# Supply.net
KiCad netlist of a schematic drawn in Altium Designer
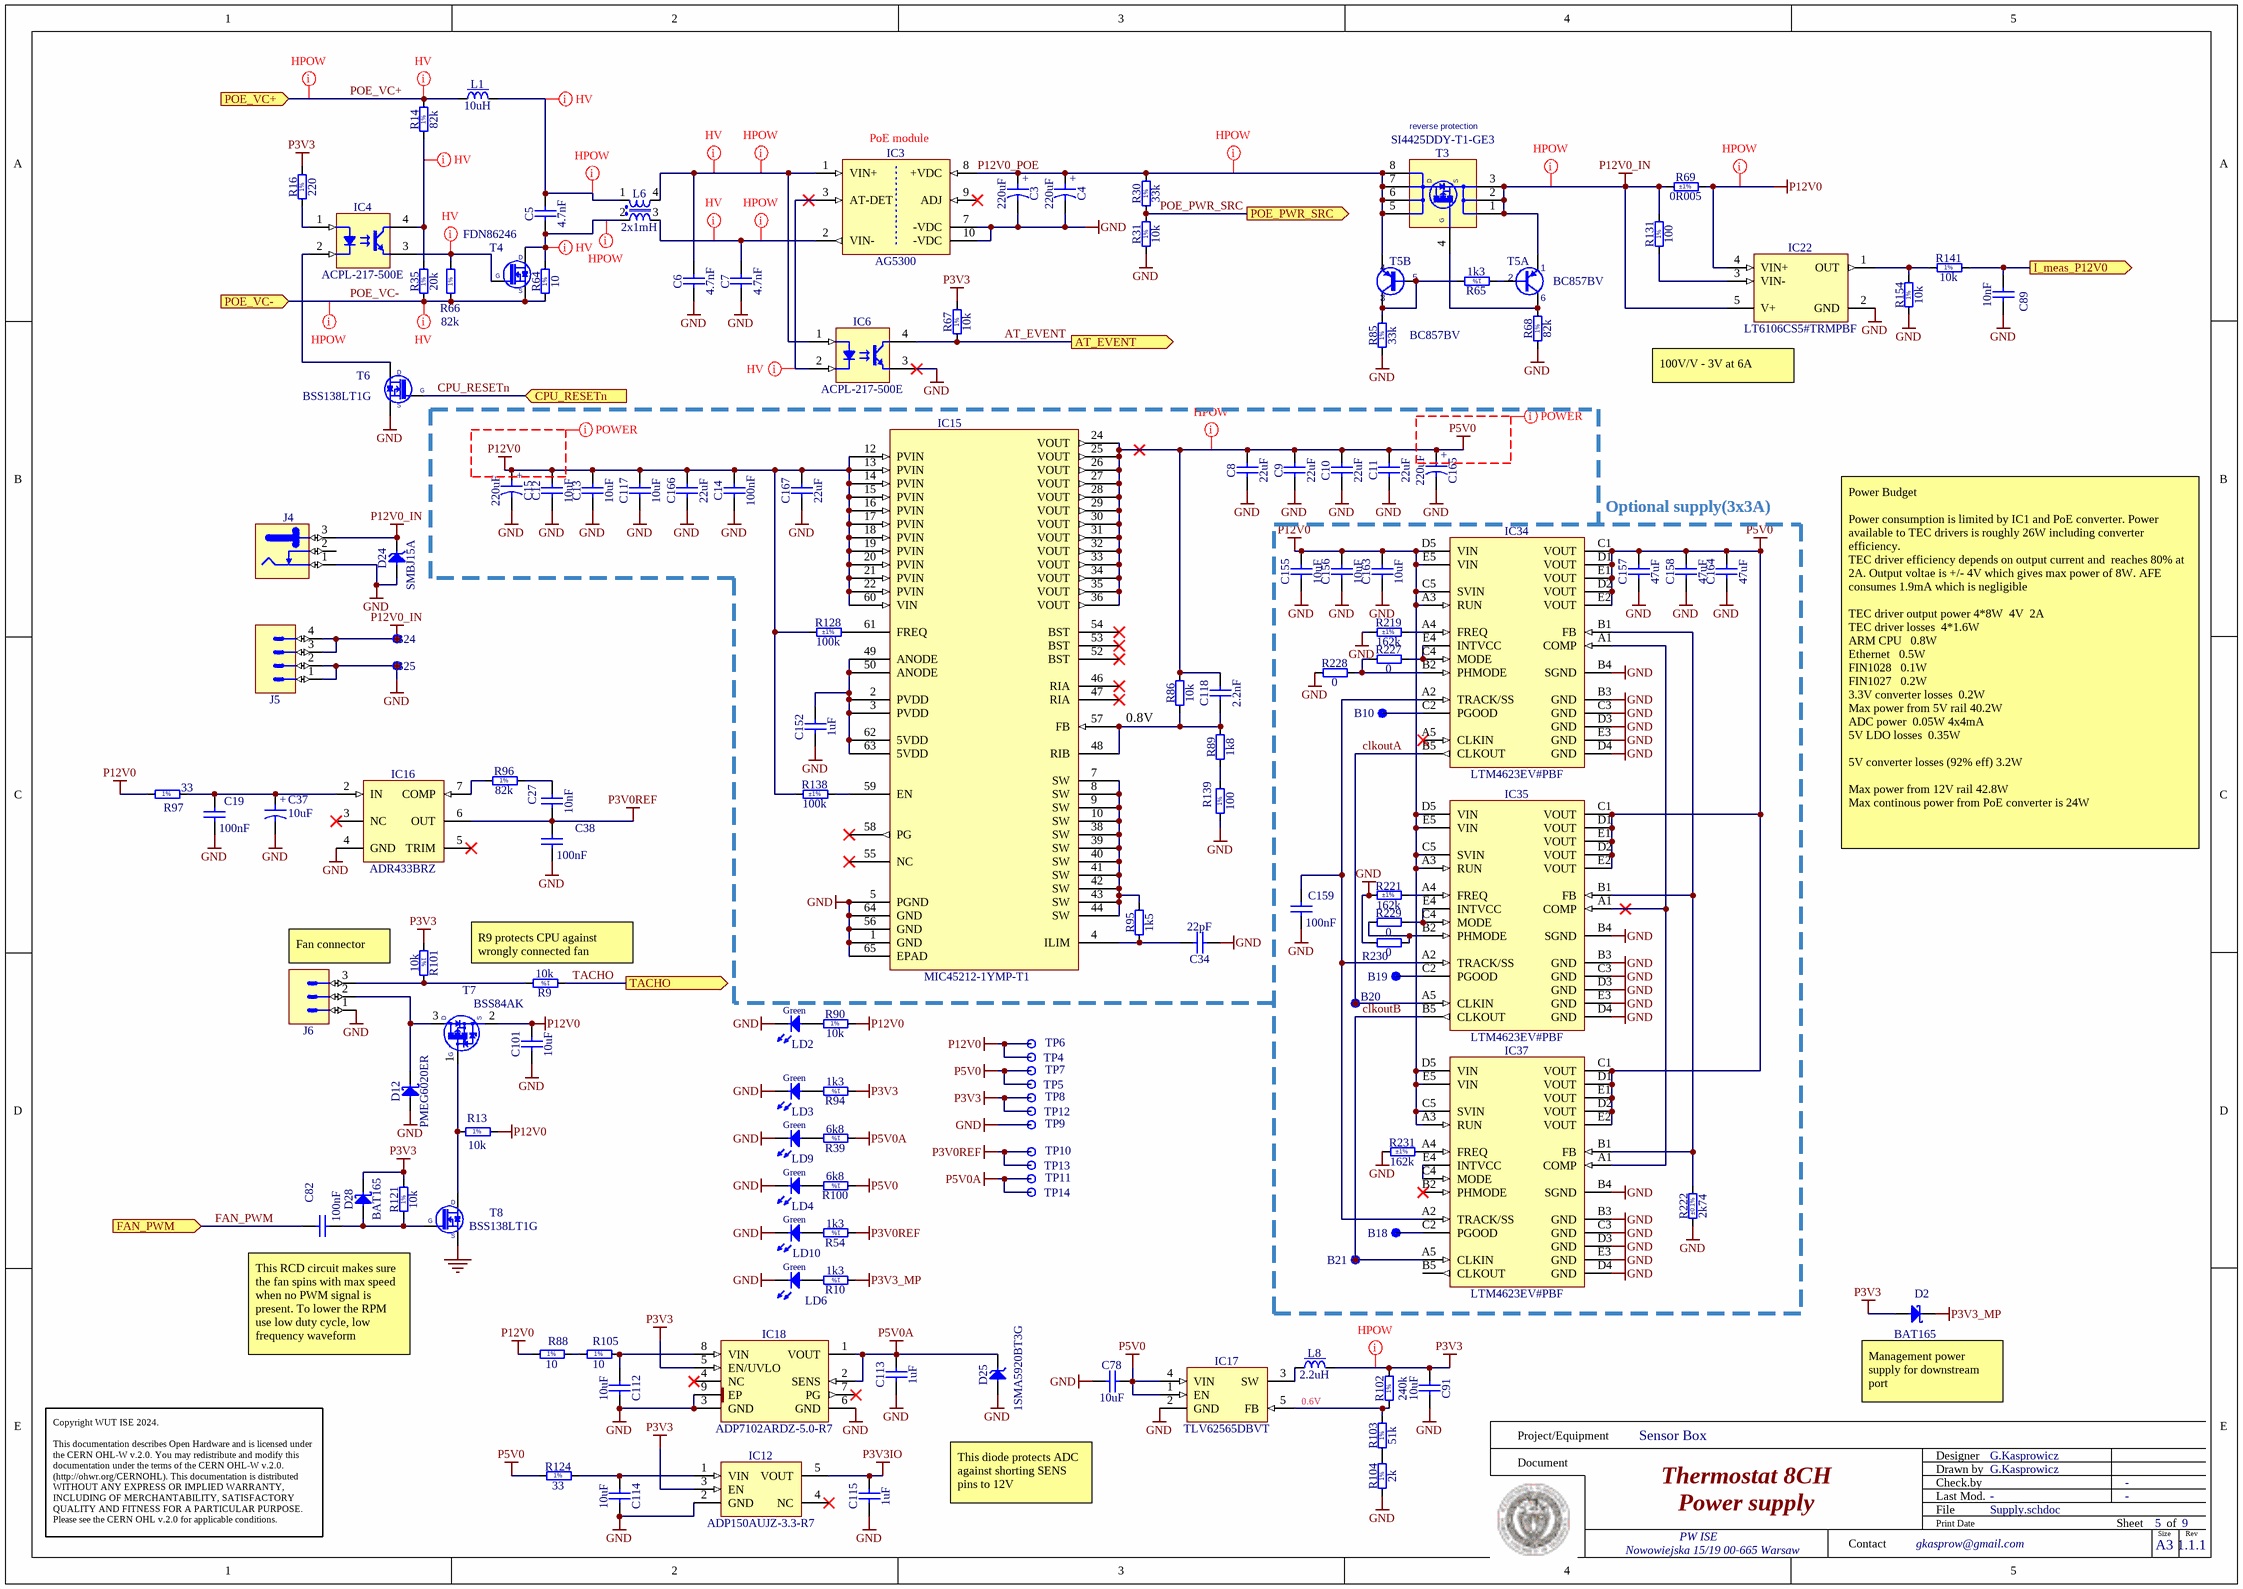
[diagram p0: Supply.schdoc]

(export (version "E")
  (design (tool "Eeschema 10.0.6"))
  (components
    (comp (ref "B10")
      (value "SMD Pad")
      (footprint "C75")
      (description "Through Hole Pad")
      (fields (field (name "PART NUMBER") "SMD_PAD_D0.75MM") (field (name "AUTHOR") "CERN DEM BC"))
      (libsource (lib "Eletro-mechanical") (part "Single SMD Pad (Round)"))
    )
    (comp (ref "B18")
      (value "SMD Pad")
      (footprint "C75")
      (description "Through Hole Pad")
      (fields (field (name "PART NUMBER") "SMD_PAD_D0.75MM") (field (name "AUTHOR") "CERN DEM BC"))
      (libsource (lib "Eletro-mechanical") (part "Single SMD Pad (Round)"))
    )
    (comp (ref "B19")
      (value "SMD Pad")
      (footprint "C75")
      (description "Through Hole Pad")
      (fields (field (name "PART NUMBER") "SMD_PAD_D0.75MM") (field (name "AUTHOR") "CERN DEM BC"))
      (libsource (lib "Eletro-mechanical") (part "Single SMD Pad (Round)"))
    )
    (comp (ref "B20")
      (value "SMD Pad")
      (footprint "C75")
      (description "Through Hole Pad")
      (fields (field (name "PART NUMBER") "SMD_PAD_D0.75MM") (field (name "AUTHOR") "CERN DEM BC"))
      (libsource (lib "Eletro-mechanical") (part "Single SMD Pad (Round)"))
    )
    (comp (ref "B21")
      (value "SMD Pad")
      (footprint "C75")
      (description "Through Hole Pad")
      (fields (field (name "PART NUMBER") "SMD_PAD_D0.75MM") (field (name "AUTHOR") "CERN DEM BC"))
      (libsource (lib "Eletro-mechanical") (part "Single SMD Pad (Round)"))
    )
    (comp (ref "B24")
      (value "SMD Pad")
      (footprint "C100")
      (description "Pad")
      (fields (field (name "PART NUMBER") "SMD_PAD_D1MM") (field (name "AUTHOR") "CERN DEM JLC"))
      (libsource (lib "Eletro-mechanical") (part "Single SMD Pad (Round)"))
    )
    (comp (ref "B25")
      (value "SMD Pad")
      (footprint "C100")
      (description "Pad")
      (fields (field (name "PART NUMBER") "SMD_PAD_D1MM") (field (name "AUTHOR") "CERN DEM JLC"))
      (libsource (lib "Eletro-mechanical") (part "Single SMD Pad (Round)"))
    )
    (comp (ref "C3")
      (value "220uF")
      (footprint "CAPMP7343X430N")
      (description "Polarised capacitor")
      (fields
        (field (name "PART NUMBER") "CTE7343-43_220UF_16V_10%")
        (field (name "VOLTAGE") "16V")
        (field (name "AUTHOR") "CERN DEM JLC")
      )
      (libsource (lib "Capacitors") (part "Capacitor - polarized"))
    )
    (comp (ref "C4")
      (value "220uF")
      (footprint "CAPMP7343X430N")
      (description "Polarised capacitor")
      (fields
        (field (name "PART NUMBER") "CTE7343-43_220UF_16V_10%")
        (field (name "VOLTAGE") "16V")
        (field (name "AUTHOR") "CERN DEM JLC")
      )
      (libsource (lib "Capacitors") (part "Capacitor - polarized"))
    )
    (comp (ref "C5")
      (value "4.7nF")
      (footprint "CAPC3216X140N")
      (description "Non-polarised capacitor")
      (fields
        (field (name "PART NUMBER") "CC1206_4.7NF_500V_10%_X7R")
        (field (name "VOLTAGE") "500V")
        (field (name "AUTHOR") "GK")
      )
      (libsource (lib "LIBRARY_SCH") (part "CAP_SMD_1206_4.7n_500V"))
    )
    (comp (ref "C6")
      (value "4.7nF")
      (footprint "CAPC3216X140N")
      (description "Non-polarised capacitor")
      (fields
        (field (name "PART NUMBER") "CC1206_4.7NF_500V_10%_X7R")
        (field (name "VOLTAGE") "500V")
        (field (name "AUTHOR") "GK")
      )
      (libsource (lib "LIBRARY_SCH") (part "CAP_SMD_1206_4.7n_500V"))
    )
    (comp (ref "C7")
      (value "4.7nF")
      (footprint "CAPC3216X140N")
      (description "Non-polarised capacitor")
      (fields
        (field (name "PART NUMBER") "CC1206_4.7NF_500V_10%_X7R")
        (field (name "VOLTAGE") "500V")
        (field (name "AUTHOR") "GK")
      )
      (libsource (lib "LIBRARY_SCH") (part "CAP_SMD_1206_4.7n_500V"))
    )
    (comp (ref "C8")
      (value "22uF")
      (footprint "CAPC2012X135N")
      (description "Non-polarised capacitor")
      (fields
        (field (name "PART NUMBER") "CC0805_22UF_16V_10%_X5R")
        (field (name "VOLTAGE") "16V")
        (field (name "AUTHOR") "CERN DEM JLC")
      )
      (libsource (lib "Capacitors") (part "Capacitor - non polarized"))
    )
    (comp (ref "C9")
      (value "22uF")
      (footprint "CAPC2012X135N")
      (description "Non-polarised capacitor")
      (fields
        (field (name "PART NUMBER") "CC0805_22UF_16V_10%_X5R")
        (field (name "VOLTAGE") "16V")
        (field (name "AUTHOR") "CERN DEM JLC")
      )
      (libsource (lib "Capacitors") (part "Capacitor - non polarized"))
    )
    (comp (ref "C10")
      (value "22uF")
      (footprint "CAPC2012X135N")
      (description "Non-polarised capacitor")
      (fields
        (field (name "PART NUMBER") "CC0805_22UF_16V_10%_X5R")
        (field (name "VOLTAGE") "16V")
        (field (name "AUTHOR") "CERN DEM JLC")
      )
      (libsource (lib "Capacitors") (part "Capacitor - non polarized"))
    )
    (comp (ref "C11")
      (value "22uF")
      (footprint "CAPC2012X135N")
      (description "Non-polarised capacitor")
      (fields
        (field (name "PART NUMBER") "CC0805_22UF_16V_10%_X5R")
        (field (name "VOLTAGE") "16V")
        (field (name "AUTHOR") "CERN DEM JLC")
      )
      (libsource (lib "Capacitors") (part "Capacitor - non polarized"))
    )
    (comp (ref "C12")
      (value "10uF")
      (footprint "CAPC2012X135N")
      (description "Non-polarised capacitor")
      (fields
        (field (name "PART NUMBER") "CC0805_10UF_16V_10%_X5R")
        (field (name "VOLTAGE") "16V")
        (field (name "AUTHOR") "CERN DEM JLC")
      )
      (libsource (lib "Capacitors") (part "Capacitor - non polarized"))
    )
    (comp (ref "C13")
      (value "10uF")
      (footprint "CAPC2012X135N")
      (description "Non-polarised capacitor")
      (fields
        (field (name "PART NUMBER") "CC0805_10UF_16V_10%_X5R")
        (field (name "VOLTAGE") "16V")
        (field (name "AUTHOR") "CERN DEM JLC")
      )
      (libsource (lib "Capacitors") (part "Capacitor - non polarized"))
    )
    (comp (ref "C14")
      (value "100nF")
      (footprint "CAPC1005X55N")
      (description "Non-polarised capacitor")
      (fields
        (field (name "PART NUMBER") "CC0402_100NF_16V_10%_X5R")
        (field (name "VOLTAGE") "16V")
        (field (name "AUTHOR") "CERN DEM JLC")
      )
      (libsource (lib "Capacitors") (part "Capacitor - non polarized"))
    )
    (comp (ref "C15")
      (value "220uF")
      (footprint "CAPMP7343X430N")
      (description "Polarised capacitor")
      (fields
        (field (name "PART NUMBER") "CTE7343-43_220UF_16V_10%")
        (field (name "VOLTAGE") "16V")
        (field (name "AUTHOR") "CERN DEM JLC")
      )
      (libsource (lib "Capacitors") (part "Capacitor - polarized"))
    )
    (comp (ref "C19")
      (value "100nF")
      (footprint "CAPC1005X55N")
      (description "Non-polarised capacitor")
      (fields
        (field (name "PART NUMBER") "CC0402_100NF_16V_10%_X5R")
        (field (name "VOLTAGE") "16V")
        (field (name "AUTHOR") "CERN DEM JLC")
      )
      (libsource (lib "Capacitors") (part "Capacitor - non polarized"))
    )
    (comp (ref "C27")
      (value "10nF")
      (footprint "CAPC1005X55N")
      (description "Non-polarised capacitor")
      (fields
        (field (name "PART NUMBER") "CC0402_10NF_25V_10%_X7R")
        (field (name "VOLTAGE") "25V")
        (field (name "AUTHOR") "CERN DEM JLC")
      )
      (libsource (lib "Capacitors") (part "Capacitor - non polarized"))
    )
    (comp (ref "C34")
      (value "22pF")
      (footprint "CAPC1005X55N")
      (description "Non-polarised capacitor")
      (fields
        (field (name "PART NUMBER") "CC0402_22PF_50V_5%_C0G")
        (field (name "VOLTAGE") "50V")
        (field (name "AUTHOR") "CERN DEM JLC")
      )
      (libsource (lib "Capacitors") (part "Capacitor - non polarized"))
    )
    (comp (ref "C37")
      (value "10uF")
      (footprint "CAPMP3216X180N")
      (description "Polarised capacitor")
      (fields
        (field (name "PART NUMBER") "CTE3216-18_10UF_16V_20%_AVX_TCJ")
        (field (name "VOLTAGE") "16V")
        (field (name "AUTHOR") "CERN DEM JLC")
      )
      (libsource (lib "Capacitors") (part "Capacitor - polarized"))
    )
    (comp (ref "C38")
      (value "100nF")
      (footprint "CAPC1005X55N")
      (description "Non-polarised capacitor")
      (fields
        (field (name "PART NUMBER") "CC0402_100NF_16V_10%_X5R")
        (field (name "VOLTAGE") "16V")
        (field (name "AUTHOR") "CERN DEM JLC")
      )
      (libsource (lib "Capacitors") (part "Capacitor - non polarized"))
    )
    (comp (ref "C78")
      (value "10uF")
      (footprint "CAPC2012X135N")
      (description "Non-polarised capacitor")
      (fields
        (field (name "PART NUMBER") "CC0805_10UF_16V_10%_X5R")
        (field (name "VOLTAGE") "16V")
        (field (name "AUTHOR") "CERN DEM JLC")
      )
      (libsource (lib "Capacitors") (part "Capacitor - non polarized"))
    )
    (comp (ref "C82")
      (value "100nF")
      (footprint "CAPC1005X55N")
      (description "Non-polarised capacitor")
      (fields
        (field (name "PART NUMBER") "CC0402_100NF_16V_10%_X5R")
        (field (name "VOLTAGE") "16V")
        (field (name "AUTHOR") "CERN DEM JLC")
      )
      (libsource (lib "Capacitors") (part "Capacitor - non polarized"))
    )
    (comp (ref "C89")
      (value "10nF")
      (footprint "CAPC1005X55N")
      (description "Non-polarised capacitor")
      (fields
        (field (name "PART NUMBER") "CC0402_10NF_25V_10%_X7R")
        (field (name "VOLTAGE") "25V")
        (field (name "AUTHOR") "CERN DEM JLC")
      )
      (libsource (lib "Capacitors") (part "Capacitor - non polarized"))
    )
    (comp (ref "C91")
      (value "10uF")
      (footprint "CAPC2012X135N")
      (description "Non-polarised capacitor")
      (fields
        (field (name "PART NUMBER") "CC0805_10UF_16V_10%_X5R")
        (field (name "VOLTAGE") "16V")
        (field (name "AUTHOR") "CERN DEM JLC")
      )
      (libsource (lib "Capacitors") (part "Capacitor - non polarized"))
    )
    (comp (ref "C101")
      (value "10uF")
      (footprint "CAPC2012X135N")
      (description "Non-polarised capacitor")
      (fields
        (field (name "PART NUMBER") "CC0805_10UF_16V_10%_X5R")
        (field (name "VOLTAGE") "16V")
        (field (name "AUTHOR") "CERN DEM JLC")
      )
      (libsource (lib "Capacitors") (part "Capacitor - non polarized"))
    )
    (comp (ref "C112")
      (value "10uF")
      (footprint "CAPC2012X135N")
      (description "Non-polarised capacitor")
      (fields
        (field (name "PART NUMBER") "CC0805_10UF_16V_10%_X5R")
        (field (name "VOLTAGE") "16V")
        (field (name "AUTHOR") "CERN DEM JLC")
      )
      (libsource (lib "Capacitors") (part "Capacitor - non polarized"))
    )
    (comp (ref "C113")
      (value "1uF")
      (footprint "CAPC1608X87N")
      (description "Non-polarised capacitor")
      (fields
        (field (name "PART NUMBER") "CC0603_1UF_25V_10%_X7R")
        (field (name "VOLTAGE") "25V")
        (field (name "AUTHOR") "CERN DEM JLC")
      )
      (libsource (lib "Capacitors") (part "Capacitor - non polarized"))
    )
    (comp (ref "C114")
      (value "10uF")
      (footprint "CAPC2012X135N")
      (description "Non-polarised capacitor")
      (fields
        (field (name "PART NUMBER") "CC0805_10UF_16V_10%_X5R")
        (field (name "VOLTAGE") "16V")
        (field (name "AUTHOR") "CERN DEM JLC")
      )
      (libsource (lib "Capacitors") (part "Capacitor - non polarized"))
    )
    (comp (ref "C115")
      (value "1uF")
      (footprint "CAPC1608X87N")
      (description "Non-polarised capacitor")
      (fields
        (field (name "PART NUMBER") "CC0603_1UF_25V_10%_X7R")
        (field (name "VOLTAGE") "25V")
        (field (name "AUTHOR") "CERN DEM JLC")
      )
      (libsource (lib "Capacitors") (part "Capacitor - non polarized"))
    )
    (comp (ref "C117")
      (value "10uF")
      (footprint "CAPC2012X135N")
      (description "Non-polarised capacitor")
      (fields
        (field (name "PART NUMBER") "CC0805_10UF_16V_10%_X5R")
        (field (name "VOLTAGE") "16V")
        (field (name "AUTHOR") "CERN DEM JLC")
      )
      (libsource (lib "Capacitors") (part "Capacitor - non polarized"))
    )
    (comp (ref "C118")
      (value "2.2nF")
      (footprint "CAPC1608X87N")
      (description "Non-polarised capacitor")
      (fields
        (field (name "PART NUMBER") "CC0603_2.2NF_50V_5%_C0G")
        (field (name "VOLTAGE") "50V")
        (field (name "AUTHOR") "CERN DEM JMW")
      )
      (libsource (lib "Capacitors") (part "Capacitor - non polarized"))
    )
    (comp (ref "C152")
      (value "1uF")
      (footprint "CAPC1608X87N")
      (description "Non-polarised capacitor")
      (fields
        (field (name "PART NUMBER") "CC0603_1UF_25V_10%_X7R")
        (field (name "VOLTAGE") "25V")
        (field (name "AUTHOR") "CERN DEM JLC")
      )
      (libsource (lib "Capacitors") (part "Capacitor - non polarized"))
    )
    (comp (ref "C155")
      (value "10uF")
      (footprint "CAPC2012X135N")
      (description "Non-polarised capacitor")
      (fields
        (field (name "PART NUMBER") "CC0805_10UF_16V_10%_X5R")
        (field (name "VOLTAGE") "16V")
        (field (name "AUTHOR") "CERN DEM JLC")
      )
      (libsource (lib "Capacitors") (part "Capacitor - non polarized"))
    )
    (comp (ref "C156")
      (value "10uF")
      (footprint "CAPC2012X135N")
      (description "Non-polarised capacitor")
      (fields
        (field (name "PART NUMBER") "CC0805_10UF_16V_10%_X5R")
        (field (name "VOLTAGE") "16V")
        (field (name "AUTHOR") "CERN DEM JLC")
      )
      (libsource (lib "Capacitors") (part "Capacitor - non polarized"))
    )
    (comp (ref "C157")
      (value "47uF")
      (footprint "CAPC2012X145N")
      (description "Non-polarised capacitor")
      (fields
        (field (name "PART NUMBER") "CC0805_47UF_10V_20%_X5R")
        (field (name "VOLTAGE") "10V")
        (field (name "AUTHOR") "CERN DEM BC")
      )
      (libsource (lib "Capacitors") (part "Capacitor - non polarized"))
    )
    (comp (ref "C158")
      (value "47uF")
      (footprint "CAPC2012X145N")
      (description "Non-polarised capacitor")
      (fields
        (field (name "PART NUMBER") "CC0805_47UF_10V_20%_X5R")
        (field (name "VOLTAGE") "10V")
        (field (name "AUTHOR") "CERN DEM BC")
      )
      (libsource (lib "Capacitors") (part "Capacitor - non polarized"))
    )
    (comp (ref "C159")
      (value "100nF")
      (footprint "CAPC1005X55N")
      (description "Non-polarised capacitor")
      (fields
        (field (name "PART NUMBER") "CC0402_100NF_16V_10%_X5R")
        (field (name "VOLTAGE") "16V")
        (field (name "AUTHOR") "CERN DEM JLC")
      )
      (libsource (lib "Capacitors") (part "Capacitor - non polarized"))
    )
    (comp (ref "C163")
      (value "10uF")
      (footprint "CAPC2012X135N")
      (description "Non-polarised capacitor")
      (fields
        (field (name "PART NUMBER") "CC0805_10UF_16V_10%_X5R")
        (field (name "VOLTAGE") "16V")
        (field (name "AUTHOR") "CERN DEM JLC")
      )
      (libsource (lib "Capacitors") (part "Capacitor - non polarized"))
    )
    (comp (ref "C164")
      (value "47uF")
      (footprint "CAPC2012X145N")
      (description "Non-polarised capacitor")
      (fields
        (field (name "PART NUMBER") "CC0805_47UF_10V_20%_X5R")
        (field (name "VOLTAGE") "10V")
        (field (name "AUTHOR") "CERN DEM BC")
      )
      (libsource (lib "Capacitors") (part "Capacitor - non polarized"))
    )
    (comp (ref "C165")
      (value "220uF")
      (footprint "CAPMP7343X430N")
      (description "Polarised capacitor")
      (fields
        (field (name "PART NUMBER") "CTE7343-43_220UF_16V_10%")
        (field (name "VOLTAGE") "16V")
        (field (name "AUTHOR") "CERN DEM JLC")
      )
      (libsource (lib "Capacitors") (part "Capacitor - polarized"))
    )
    (comp (ref "C166")
      (value "22uF")
      (footprint "CAPC2012X135N")
      (description "Non-polarised capacitor")
      (fields
        (field (name "PART NUMBER") "CC0805_22UF_16V_10%_X5R")
        (field (name "VOLTAGE") "16V")
        (field (name "AUTHOR") "CERN DEM JLC")
      )
      (libsource (lib "Capacitors") (part "Capacitor - non polarized"))
    )
    (comp (ref "C167")
      (value "22uF")
      (footprint "CAPC2012X135N")
      (description "Non-polarised capacitor")
      (fields
        (field (name "PART NUMBER") "CC0805_22UF_16V_10%_X5R")
        (field (name "VOLTAGE") "16V")
        (field (name "AUTHOR") "CERN DEM JLC")
      )
      (libsource (lib "Capacitors") (part "Capacitor - non polarized"))
    )
    (comp (ref "D2")
      (value "BAT165")
      (footprint "SOD2512X110N")
      (description "Schottky Diode")
      (fields
        (field (name "VOLTAGE") "40V")
        (field (name "POWER") "750mA")
        (field (name "AUTHOR") "CERN DEM JLC")
      )
      (libsource (lib "ICs And Semiconductors") (part "Diode Schottky"))
    )
    (comp (ref "D12")
      (value "PMEG6020ER")
      (footprint "SODFL3517X110N")
      (description "Schottky Diode")
      (fields
        (field (name "VOLTAGE") "60V")
        (field (name "POWER") "2A")
        (field (name "AUTHOR") "CERN DEM JMW")
      )
      (libsource (lib "ICs And Semiconductors") (part "Diode Schottky"))
    )
    (comp (ref "D24")
      (value "SMBJ15A")
      (footprint "DIOM5336X265N")
      (description "Zener Diode")
      (fields
        (field (name "VOLTAGE") "15V")
        (field (name "POWER") "600W")
        (field (name "AUTHOR") "CERN DEM JLC")
      )
      (libsource (lib "ICs And Semiconductors") (part "Diode Zener"))
    )
    (comp (ref "D25")
      (value "1SMA5920BT3G")
      (footprint "DIOM5226X220N")
      (description "6.2V 1.5 Watt Plastic Surface Mount Zener Voltage Regulators")
      (fields (field (name "VOLTAGE") "6.2V") (field (name "POWER") "1.5W") (field (name "AUTHOR") "GK"))
      (libsource (lib "Diodes") (part "D_Zener_1SMA5920BT3G"))
    )
    (comp (ref "D28")
      (value "BAT165")
      (footprint "SOD2512X110N")
      (description "Schottky Diode")
      (fields
        (field (name "VOLTAGE") "40V")
        (field (name "POWER") "750mA")
        (field (name "AUTHOR") "CERN DEM JLC")
      )
      (libsource (lib "ICs And Semiconductors") (part "Diode Schottky"))
    )
    (comp (ref "IC3")
      (value "AG5300")
      (footprint "SILVERTEL_AG5300")
      (description "Power-over-Ethernet Plus (POE+) Module")
      (fields (field (name "MANUFACTURER") "SILVERTEL") (field (name "AUTHOR") "CERN DEM JLC"))
      (libsource (lib "ICs And Semiconductors") (part "AG5300"))
    )
    (comp (ref "IC4")
      (value "ACPL-217-500E")
      (footprint "SOIC127P700X242-4N")
      (description "Single Optocoupler")
      (fields (field (name "MANUFACTURER") "AVAGO TECHNOLOGIES") (field (name "AUTHOR") "CERN DEM JLC"))
      (libsource (lib "ICs And Semiconductors") (part "Optocoupler Type7"))
    )
    (comp (ref "IC6")
      (value "ACPL-217-500E")
      (footprint "SOIC127P700X242-4N")
      (description "Single Optocoupler")
      (fields (field (name "MANUFACTURER") "AVAGO TECHNOLOGIES") (field (name "AUTHOR") "CERN DEM JLC"))
      (libsource (lib "ICs And Semiconductors") (part "Optocoupler Type7"))
    )
    (comp (ref "IC12")
      (value "ADP150AUJZ-3.3-R7")
      (footprint "SOT95P280X90-5N")
      (description "Ultralow Noise, 150 mA CMOS Linear Regulator")
      (fields (field (name "MANUFACTURER") "ANALOG DEVICES") (field (name "AUTHOR") "CERN DEM JLC"))
      (libsource (lib "ICs And Semiconductors") (part "ADP150AUJZ"))
    )
    (comp (ref "IC15")
      (value "MIC45212-1YMP-T1")
      (footprint "MICROCHIP_QFN64_12X12")
      (description "0.8V to 85% PVIN (4.5...26V), 14A Synchronous Step-Down Regulator Module")
      (fields (field (name "MANUFACTURER") "MICROCHIP TECHNOLOGY") (field (name "AUTHOR") "GK"))
      (libsource (lib "Regulators_SMPS") (part "PM_MIC45212-1"))
    )
    (comp (ref "IC16")
      (value "ADR433BRZ")
      (footprint "SOIC127P600X175-8N")
      (fields (field (name "MANUFACTURER") "ANALOG DEVICES") (field (name "AUTHOR") "CERN DEM JMW"))
      (libsource (lib "ICs And Semiconductors") (part "ADR433"))
    )
    (comp (ref "IC17")
      (value "TLV62565DBVT")
      (footprint "SOT95P280X145-5N")
      (description "1.5A High Efficiency Step-Down Converter, Adjustable Output Voltage")
      (fields (field (name "MANUFACTURER") "TEXAS INSTRUMENTS") (field (name "AUTHOR") "CERN DEM JMW"))
      (libsource (lib "ICs And Semiconductors") (part "TLV62565"))
    )
    (comp (ref "IC18")
      (value "ADP7102ARDZ-5.0-R7")
      (footprint "SOIC127P600X175-9N-R241X309")
      (description "300 mA, Low Noise, CMOS LDO Linear Regulator")
      (fields (field (name "MANUFACTURER") "ANALOG DEVICES") (field (name "AUTHOR") "CERN DEM JLC"))
      (libsource (lib "ICs And Semiconductors") (part "ADP7102ARDZ-X.X-R7"))
    )
    (comp (ref "IC22")
      (value "LT6106CS5#TRMPBF")
      (footprint "SOT95P280X145-5N")
      (description "Current Shunt Monitor -16V to +80V Common-Mode Range")
      (fields (field (name "MANUFACTURER") "ANALOG DEVICES") (field (name "AUTHOR") "GK"))
      (libsource (lib "ICs_Analog_Interfaces") (part "AMP_LT6106"))
    )
    (comp (ref "IC34")
      (value "LTM4623EV#PBF")
      (footprint "LGA25C127P5X5_625X625X192")
      (description "4V-20V to 0.6V-5.5V, Iout 3A Step-Down DC/DC uModule Regulator")
      (fields (field (name "MANUFACTURER") "LINEAR TECHNOLOGY") (field (name "AUTHOR") "CERN DEM JMW"))
      (libsource (lib "ICs And Semiconductors") (part "LTM4623"))
    )
    (comp (ref "IC35")
      (value "LTM4623EV#PBF")
      (footprint "LGA25C127P5X5_625X625X192")
      (description "4V-20V to 0.6V-5.5V, Iout 3A Step-Down DC/DC uModule Regulator")
      (fields (field (name "MANUFACTURER") "LINEAR TECHNOLOGY") (field (name "AUTHOR") "CERN DEM JMW"))
      (libsource (lib "ICs And Semiconductors") (part "LTM4623"))
    )
    (comp (ref "IC37")
      (value "LTM4623EV#PBF")
      (footprint "LGA25C127P5X5_625X625X192")
      (description "4V-20V to 0.6V-5.5V, Iout 3A Step-Down DC/DC uModule Regulator")
      (fields (field (name "MANUFACTURER") "LINEAR TECHNOLOGY") (field (name "AUTHOR") "CERN DEM JMW"))
      (libsource (lib "ICs And Semiconductors") (part "LTM4623"))
    )
    (comp (ref "J4")
      (value "Jack")
      (footprint "SWITCHCRAFT_L712RA")
      (description "24V /3. 5A, 2.1mm Diameter Pin, SMD DC Power Supply Connector With  Break Contact")
      (fields
        (field (name "PART NUMBER") "SWITCHCRAFT_712RA")
        (field (name "MANUFACTURER") "SWITCHCRAFT")
        (field (name "AUTHOR") "GK")
      )
      (libsource (lib "LIBRARY_SCH") (part "CON_DC_5A_THT_RA"))
    )
    (comp (ref "J5")
      (value "Mini-Fit Jr.™")
      (footprint "MOLEX_39-30-0040")
      (description "Connector 4 Male")
      (fields
        (field (name "PART NUMBER") "MOLEX_39-30-0040")
        (field (name "MANUFACTURER") "MOLEX")
        (field (name "AUTHOR") "CERN DEM JLC")
      )
      (libsource (lib "Connectors") (part "Connector 4 Male"))
    )
    (comp (ref "J6")
      (value "KK®")
      (footprint "MOLEX_22-27-2031")
      (description "Connector 3 Male")
      (fields
        (field (name "PART NUMBER") "MOLEX_22-27-2031")
        (field (name "MANUFACTURER") "MOLEX")
        (field (name "AUTHOR") "CERN DEM JLC")
      )
      (libsource (lib "Connectors") (part "Connector 3 Male"))
    )
    (comp (ref "L1")
      (value "10uH")
      (footprint "IND_MURATA-PS_8400")
      (description "Inductor With Core")
      (fields
        (field (name "PART NUMBER") "IND_10UH_10%_MURATA-PS_8400")
        (field (name "POWER") "950mA")
        (field (name "AUTHOR") "CERN DEM JLC")
      )
      (libsource (lib "Inductors & Transformers") (part "Inductor With Magnetic core"))
    )
    (comp (ref "L6")
      (value "2x1mH")
      (footprint "IND_WURTH_WE-SL2")
      (description "Inductor Common Mode")
      (fields
        (field (name "PART NUMBER") "IND_1MH_50%_WURTH_WE-SL2-744222")
        (field (name "POWER") "800mA")
        (field (name "AUTHOR") "CERN DEM JLC")
      )
      (libsource (lib "Inductors & Transformers") (part "Inductor Common Mode 1Dot-4 2Dot-3"))
    )
    (comp (ref "L8")
      (value "2.2uH")
      (footprint "IND_MURATA_LQH44PN_P0")
      (description "Inductor With Core")
      (fields
        (field (name "PART NUMBER") "IND_2.2UH_20%_MURATA_LQH44PN2R2MP0L")
        (field (name "POWER") "1.8A")
        (field (name "AUTHOR") "CERN DEM JLC")
      )
      (libsource (lib "Inductors & Transformers") (part "Inductor With Magnetic core"))
    )
    (comp (ref "LD2")
      (value "Green")
      (footprint "LED_KINGBRIGHT_KPH-1608CGCK")
      (description "LED Green 1C 2A")
      (fields
        (field (name "PART NUMBER") "LED_KINGBRIGHT_KPH-1608CGCK")
        (field (name "MANUFACTURER") "KINGBRIGHT")
        (field (name "AUTHOR") "CERN DEM JLC")
      )
      (libsource (lib "ICs And Semiconductors") (part "LED Green 1C 2A"))
    )
    (comp (ref "LD3")
      (value "Green")
      (footprint "LED_KINGBRIGHT_KPH-1608CGCK")
      (description "LED Green 1C 2A")
      (fields
        (field (name "PART NUMBER") "LED_KINGBRIGHT_KPH-1608CGCK")
        (field (name "MANUFACTURER") "KINGBRIGHT")
        (field (name "AUTHOR") "CERN DEM JLC")
      )
      (libsource (lib "ICs And Semiconductors") (part "LED Green 1C 2A"))
    )
    (comp (ref "LD4")
      (value "Green")
      (footprint "LED_KINGBRIGHT_KPH-1608CGCK")
      (description "LED Green 1C 2A")
      (fields
        (field (name "PART NUMBER") "LED_KINGBRIGHT_KPH-1608CGCK")
        (field (name "MANUFACTURER") "KINGBRIGHT")
        (field (name "AUTHOR") "CERN DEM JLC")
      )
      (libsource (lib "ICs And Semiconductors") (part "LED Green 1C 2A"))
    )
    (comp (ref "LD6")
      (value "Green")
      (footprint "LED_KINGBRIGHT_KPH-1608CGCK")
      (description "LED Green 1C 2A")
      (fields
        (field (name "PART NUMBER") "LED_KINGBRIGHT_KPH-1608CGCK")
        (field (name "MANUFACTURER") "KINGBRIGHT")
        (field (name "AUTHOR") "CERN DEM JLC")
      )
      (libsource (lib "ICs And Semiconductors") (part "LED Green 1C 2A"))
    )
    (comp (ref "LD9")
      (value "Green")
      (footprint "LED_KINGBRIGHT_KPH-1608CGCK")
      (description "LED Green 1C 2A")
      (fields
        (field (name "PART NUMBER") "LED_KINGBRIGHT_KPH-1608CGCK")
        (field (name "MANUFACTURER") "KINGBRIGHT")
        (field (name "AUTHOR") "CERN DEM JLC")
      )
      (libsource (lib "ICs And Semiconductors") (part "LED Green 1C 2A"))
    )
    (comp (ref "LD10")
      (value "Green")
      (footprint "LED_KINGBRIGHT_KPH-1608CGCK")
      (description "LED Green 1C 2A")
      (fields
        (field (name "PART NUMBER") "LED_KINGBRIGHT_KPH-1608CGCK")
        (field (name "MANUFACTURER") "KINGBRIGHT")
        (field (name "AUTHOR") "CERN DEM JLC")
      )
      (libsource (lib "ICs And Semiconductors") (part "LED Green 1C 2A"))
    )
    (comp (ref "R9")
      (value "10k")
      (footprint "RESC1005X40N")
      (description "Resistor - 1%")
      (fields
        (field (name "PART NUMBER") "R0402_10K_1%_0.0625W_100PPM")
        (field (name "POWER") "0.0625W")
        (field (name "AUTHOR") "CERN DEM JLC")
      )
      (libsource (lib "Resistors") (part "Resistor - 1%"))
    )
    (comp (ref "R10")
      (value "1k3")
      (footprint "RESC1608X55N")
      (description "Resistor - 1%")
      (fields
        (field (name "PART NUMBER") "R0603_1K3_1%_0.1W_100PPM")
        (field (name "POWER") "0.1W")
        (field (name "AUTHOR") "CERN DEM JLC")
      )
      (libsource (lib "Resistors") (part "Resistor - 1%"))
    )
    (comp (ref "R13")
      (value "10k")
      (footprint "RESC1005X40N")
      (description "Resistor - 1%")
      (fields
        (field (name "PART NUMBER") "R0402_10K_1%_0.0625W_100PPM")
        (field (name "POWER") "0.0625W")
        (field (name "AUTHOR") "CERN DEM JLC")
      )
      (libsource (lib "Resistors") (part "Resistor - 1%"))
    )
    (comp (ref "R14")
      (value "82k")
      (footprint "RESC1608X55N")
      (description "Resistor - 1%")
      (fields
        (field (name "PART NUMBER") "R0603_82K_1%_0.1W_100PPM")
        (field (name "POWER") "0.1W")
        (field (name "AUTHOR") "CERN DEM JLC")
      )
      (libsource (lib "Resistors") (part "Resistor - 1%"))
    )
    (comp (ref "R16")
      (value "220")
      (footprint "RESC1608X55N")
      (description "Resistor - 1%")
      (fields
        (field (name "PART NUMBER") "R0603_220R_1%_0.1W_100PPM")
        (field (name "POWER") "0.1W")
        (field (name "AUTHOR") "CERN DEM JLC")
      )
      (libsource (lib "Resistors") (part "Resistor - 1%"))
    )
    (comp (ref "R30")
      (value "33k")
      (footprint "RESC1005X40N")
      (description "Resistor - 1%")
      (fields
        (field (name "PART NUMBER") "R0402_33K_1%_0.0625W_100PPM")
        (field (name "POWER") "0.0625W")
        (field (name "AUTHOR") "CERN DEM JLC")
      )
      (libsource (lib "Resistors") (part "Resistor - 1%"))
    )
    (comp (ref "R31")
      (value "10k")
      (footprint "RESC1005X40N")
      (description "Resistor - 1%")
      (fields
        (field (name "PART NUMBER") "R0402_10K_1%_0.0625W_100PPM")
        (field (name "POWER") "0.0625W")
        (field (name "AUTHOR") "CERN DEM JLC")
      )
      (libsource (lib "Resistors") (part "Resistor - 1%"))
    )
    (comp (ref "R35")
      (value "20k")
      (footprint "RESC1005X40N")
      (description "Resistor - 1%")
      (fields
        (field (name "PART NUMBER") "R0402_20K_1%_0.0625W_100PPM")
        (field (name "POWER") "0.0625W")
        (field (name "AUTHOR") "CERN DEM JLC")
      )
      (libsource (lib "Resistors") (part "Resistor - 1%"))
    )
    (comp (ref "R39")
      (value "6k8")
      (footprint "RESC1005X40N")
      (description "Resistor - 1%")
      (fields
        (field (name "PART NUMBER") "R0402_6K8_1%_0.0625W_100PPM")
        (field (name "POWER") "0.0625W")
        (field (name "AUTHOR") "CERN DEM JLC")
      )
      (libsource (lib "Resistors") (part "Resistor - 1%"))
    )
    (comp (ref "R54")
      (value "1k3")
      (footprint "RESC1608X55N")
      (description "Resistor - 1%")
      (fields
        (field (name "PART NUMBER") "R0603_1K3_1%_0.1W_100PPM")
        (field (name "POWER") "0.1W")
        (field (name "AUTHOR") "CERN DEM JLC")
      )
      (libsource (lib "Resistors") (part "Resistor - 1%"))
    )
    (comp (ref "R64")
      (value "10")
      (footprint "RESC2012X60N")
      (description "Resistor - 1%")
      (fields
        (field (name "PART NUMBER") "R0805_10R_1%_0.125W_200PPM")
        (field (name "POWER") "0.125W")
        (field (name "AUTHOR") "CERN DEM JLC")
      )
      (libsource (lib "Resistors") (part "Resistor - 1%"))
    )
    (comp (ref "R65")
      (value "1k3")
      (footprint "RESC1608X55N")
      (description "Resistor - 1%")
      (fields
        (field (name "PART NUMBER") "R0603_1K3_1%_0.1W_100PPM")
        (field (name "POWER") "0.1W")
        (field (name "AUTHOR") "CERN DEM JLC")
      )
      (libsource (lib "Resistors") (part "Resistor - 1%"))
    )
    (comp (ref "R66")
      (value "82k")
      (footprint "RESC1608X55N")
      (description "Resistor - 1%")
      (fields
        (field (name "PART NUMBER") "R0603_82K_1%_0.1W_100PPM")
        (field (name "POWER") "0.1W")
        (field (name "AUTHOR") "CERN DEM JLC")
      )
      (libsource (lib "Resistors") (part "Resistor - 1%"))
    )
    (comp (ref "R67")
      (value "10k")
      (footprint "RESC1005X40N")
      (description "Resistor - 1%")
      (fields
        (field (name "PART NUMBER") "R0402_10K_1%_0.0625W_100PPM")
        (field (name "POWER") "0.0625W")
        (field (name "AUTHOR") "CERN DEM JLC")
      )
      (libsource (lib "Resistors") (part "Resistor - 1%"))
    )
    (comp (ref "R68")
      (value "82k")
      (footprint "RESC1608X55N")
      (description "Resistor - 1%")
      (fields
        (field (name "PART NUMBER") "R0603_82K_1%_0.1W_100PPM")
        (field (name "POWER") "0.1W")
        (field (name "AUTHOR") "CERN DEM JLC")
      )
      (libsource (lib "Resistors") (part "Resistor - 1%"))
    )
    (comp (ref "R69")
      (value "0R005")
      (footprint "RESC3216X80N")
      (description "Resistor - 1%")
      (fields
        (field (name "TOLERANCE") "±1%")
        (field (name "PART NUMBER") "R1206_0R005_1%_1W_100PPM_TT_LRMAM1206")
        (field (name "POWER") "1W")
        (field (name "AUTHOR") "CERN DEM BC")
      )
      (libsource (lib "") (part "Resistor - 1%_1"))
    )
    (comp (ref "R85")
      (value "33k")
      (footprint "RESC1005X40N")
      (description "Resistor - 1%")
      (fields
        (field (name "PART NUMBER") "R0402_33K_1%_0.0625W_100PPM")
        (field (name "POWER") "0.0625W")
        (field (name "AUTHOR") "CERN DEM JLC")
      )
      (libsource (lib "Resistors") (part "Resistor - 1%"))
    )
    (comp (ref "R86")
      (value "10k")
      (footprint "RESC1005X40N")
      (description "Resistor - 1%")
      (fields
        (field (name "PART NUMBER") "R0402_10K_1%_0.0625W_100PPM")
        (field (name "POWER") "0.0625W")
        (field (name "AUTHOR") "CERN DEM JLC")
      )
      (libsource (lib "") (part "Resistor - 1%_1"))
    )
    (comp (ref "R88")
      (value "10")
      (footprint "RESC2012X60N")
      (description "Resistor - 1%")
      (fields
        (field (name "PART NUMBER") "R0805_10R_1%_0.125W_200PPM")
        (field (name "POWER") "0.125W")
        (field (name "AUTHOR") "CERN DEM JLC")
      )
      (libsource (lib "Resistors") (part "Resistor - 1%"))
    )
    (comp (ref "R89")
      (value "1k8")
      (footprint "RESC1608X55N")
      (description "Resistor - 1%")
      (fields
        (field (name "PART NUMBER") "R0603_1K8_1%_0.1W_100PPM")
        (field (name "POWER") "0.1W")
        (field (name "AUTHOR") "CERN DEM JLC")
      )
      (libsource (lib "Resistors") (part "Resistor - 1%"))
    )
    (comp (ref "R90")
      (value "10k")
      (footprint "RESC1005X40N")
      (description "Resistor - 1%")
      (fields
        (field (name "PART NUMBER") "R0402_10K_1%_0.0625W_100PPM")
        (field (name "POWER") "0.0625W")
        (field (name "AUTHOR") "CERN DEM JLC")
      )
      (libsource (lib "Resistors") (part "Resistor - 1%"))
    )
    (comp (ref "R94")
      (value "1k3")
      (footprint "RESC1608X55N")
      (description "Resistor - 1%")
      (fields
        (field (name "PART NUMBER") "R0603_1K3_1%_0.1W_100PPM")
        (field (name "POWER") "0.1W")
        (field (name "AUTHOR") "CERN DEM JLC")
      )
      (libsource (lib "Resistors") (part "Resistor - 1%"))
    )
    (comp (ref "R95")
      (value "1k5")
      (footprint "RESC1005X40N")
      (description "Resistor - 1%")
      (fields
        (field (name "PART NUMBER") "R0402_1K5_1%_0.0625W_100PPM")
        (field (name "POWER") "0.0625W")
        (field (name "AUTHOR") "CERN DEM JLC")
      )
      (libsource (lib "") (part "Resistor - 1%_1"))
    )
    (comp (ref "R96")
      (value "82k")
      (footprint "RESC1608X55N")
      (description "Resistor - 1%")
      (fields
        (field (name "PART NUMBER") "R0603_82K_1%_0.1W_100PPM")
        (field (name "POWER") "0.1W")
        (field (name "AUTHOR") "CERN DEM JLC")
      )
      (libsource (lib "Resistors") (part "Resistor - 1%"))
    )
    (comp (ref "R97")
      (value "33")
      (footprint "RESC1005X40N")
      (description "Resistor - 1%")
      (fields
        (field (name "PART NUMBER") "R0402_33R_1%_0.0625W_100PPM")
        (field (name "POWER") "0.0625W")
        (field (name "AUTHOR") "CERN DEM JLC")
      )
      (libsource (lib "Resistors") (part "Resistor - 1%"))
    )
    (comp (ref "R100")
      (value "6k8")
      (footprint "RESC1005X40N")
      (description "Resistor - 1%")
      (fields
        (field (name "PART NUMBER") "R0402_6K8_1%_0.0625W_100PPM")
        (field (name "POWER") "0.0625W")
        (field (name "AUTHOR") "CERN DEM JLC")
      )
      (libsource (lib "Resistors") (part "Resistor - 1%"))
    )
    (comp (ref "R101")
      (value "10k")
      (footprint "RESC1005X40N")
      (description "Resistor - 1%")
      (fields
        (field (name "PART NUMBER") "R0402_10K_1%_0.0625W_100PPM")
        (field (name "POWER") "0.0625W")
        (field (name "AUTHOR") "CERN DEM JLC")
      )
      (libsource (lib "Resistors") (part "Resistor - 1%"))
    )
    (comp (ref "R102")
      (value "240k")
      (footprint "RESC1005X40N")
      (description "Resistor - 1%")
      (fields
        (field (name "PART NUMBER") "R0402_240K_1%_0.0625W_100PPM")
        (field (name "POWER") "0.0625W")
        (field (name "AUTHOR") "CERN DEM JLC")
      )
      (libsource (lib "Resistors") (part "Resistor - 1%"))
    )
    (comp (ref "R103")
      (value "51k")
      (footprint "RESC1005X40N")
      (description "Resistor - 1%")
      (fields
        (field (name "PART NUMBER") "R0402_51K_1%_0.0625W_100PPM")
        (field (name "POWER") "0.0625W")
        (field (name "AUTHOR") "CERN DEM JLC")
      )
      (libsource (lib "Resistors") (part "Resistor - 1%"))
    )
    (comp (ref "R104")
      (value "2k")
      (footprint "RESC1005X40N")
      (description "Resistor - 1%")
      (fields
        (field (name "PART NUMBER") "R0402_2K_1%_0.0625W_100PPM")
        (field (name "POWER") "0.0625W")
        (field (name "AUTHOR") "CERN DEM JLC")
      )
      (libsource (lib "Resistors") (part "Resistor - 1%"))
    )
    (comp (ref "R105")
      (value "10")
      (footprint "RESC2012X60N")
      (description "Resistor - 1%")
      (fields
        (field (name "PART NUMBER") "R0805_10R_1%_0.125W_200PPM")
        (field (name "POWER") "0.125W")
        (field (name "AUTHOR") "CERN DEM JLC")
      )
      (libsource (lib "Resistors") (part "Resistor - 1%"))
    )
    (comp (ref "R121")
      (value "10k")
      (footprint "RESC1005X40N")
      (description "Resistor - 1%")
      (fields
        (field (name "PART NUMBER") "R0402_10K_1%_0.0625W_100PPM")
        (field (name "POWER") "0.0625W")
        (field (name "AUTHOR") "CERN DEM JLC")
      )
      (libsource (lib "Resistors") (part "Resistor - 1%"))
    )
    (comp (ref "R124")
      (value "33")
      (footprint "RESC1005X40N")
      (description "Resistor - 1%")
      (fields
        (field (name "PART NUMBER") "R0402_33R_1%_0.0625W_100PPM")
        (field (name "POWER") "0.0625W")
        (field (name "AUTHOR") "CERN DEM JLC")
      )
      (libsource (lib "Resistors") (part "Resistor - 1%"))
    )
    (comp (ref "R128")
      (value "100k")
      (footprint "RESC1005X40N")
      (description "Resistor - 1%")
      (fields
        (field (name "TOLERANCE") "±1%")
        (field (name "PART NUMBER") "R0402_100K_1%_0.0625W_100PPM")
        (field (name "POWER") "0.0625W")
        (field (name "AUTHOR") "CERN DEM JLC")
      )
      (libsource (lib "") (part "Resistor - 1%_1"))
    )
    (comp (ref "R131")
      (value "100")
      (footprint "RESC1005X40N")
      (description "Resistor - 1%")
      (fields
        (field (name "PART NUMBER") "R0402_100R_1%_0.0625W_100PPM")
        (field (name "POWER") "0.0625W")
        (field (name "AUTHOR") "CERN DEM JLC")
      )
      (libsource (lib "Resistors") (part "Resistor - 1%"))
    )
    (comp (ref "R138")
      (value "100k")
      (footprint "RESC1005X40N")
      (description "Resistor - 1%")
      (fields
        (field (name "TOLERANCE") "±1%")
        (field (name "PART NUMBER") "R0402_100K_1%_0.0625W_100PPM")
        (field (name "POWER") "0.0625W")
        (field (name "AUTHOR") "CERN DEM JLC")
      )
      (libsource (lib "") (part "Resistor - 1%_1"))
    )
    (comp (ref "R139")
      (value "100")
      (footprint "RESC1005X40N")
      (description "Resistor - 1%")
      (fields
        (field (name "PART NUMBER") "R0402_100R_1%_0.0625W_100PPM")
        (field (name "POWER") "0.0625W")
        (field (name "AUTHOR") "CERN DEM JLC")
      )
      (libsource (lib "Resistors") (part "Resistor - 1%"))
    )
    (comp (ref "R141")
      (value "10k")
      (footprint "RESC1005X40N")
      (description "Resistor - 1%")
      (fields
        (field (name "PART NUMBER") "R0402_10K_1%_0.0625W_100PPM")
        (field (name "POWER") "0.0625W")
        (field (name "AUTHOR") "CERN DEM JLC")
      )
      (libsource (lib "Resistors") (part "Resistor - 1%"))
    )
    (comp (ref "R154")
      (value "10k")
      (footprint "RESC1005X40N")
      (description "Resistor - 1%")
      (fields
        (field (name "PART NUMBER") "R0402_10K_1%_0.0625W_100PPM")
        (field (name "POWER") "0.0625W")
        (field (name "AUTHOR") "CERN DEM JLC")
      )
      (libsource (lib "Resistors") (part "Resistor - 1%"))
    )
    (comp (ref "R219")
      (value "162k")
      (footprint "RESC1005X40N")
      (description "Resistor - 1%")
      (fields
        (field (name "TOLERANCE") "±1%")
        (field (name "PART NUMBER") "R0402_162K_1%_0.063W_100PPM")
        (field (name "POWER") "0.063W")
        (field (name "AUTHOR") "CERN DEM BC")
      )
      (libsource (lib "") (part "Resistor - 1%_1"))
    )
    (comp (ref "R221")
      (value "162k")
      (footprint "RESC1005X40N")
      (description "Resistor - 1%")
      (fields
        (field (name "TOLERANCE") "±1%")
        (field (name "PART NUMBER") "R0402_162K_1%_0.063W_100PPM")
        (field (name "POWER") "0.063W")
        (field (name "AUTHOR") "CERN DEM BC")
      )
      (libsource (lib "") (part "Resistor - 1%_1"))
    )
    (comp (ref "R222")
      (value "2k74")
      (footprint "RESC1608X55N")
      (description "Resistor - 0.1%")
      (fields
        (field (name "TOLERANCE") "±0.1%")
        (field (name "PART NUMBER") "R0603_2K74_0.1%_0.063W_10PPM")
        (field (name "POWER") "0.063W")
        (field (name "AUTHOR") "CERN DEM JLC")
      )
      (libsource (lib "Resistors") (part "Resistor - 0.1%"))
    )
    (comp (ref "R227")
      (value "0")
      (footprint "RESC1005X40N")
      (description "Resistor")
      (fields
        (field (name "PART NUMBER") "R0402_0R_JUMPER")
        (field (name "MANUFACTURER") "GENERIC")
        (field (name "AUTHOR") "CERN DEM JLC")
      )
      (libsource (lib "Resistors") (part "Resistor"))
    )
    (comp (ref "R228")
      (value "0")
      (footprint "RESC1005X40N")
      (description "Resistor")
      (fields
        (field (name "PART NUMBER") "R0402_0R_JUMPER")
        (field (name "MANUFACTURER") "GENERIC")
        (field (name "AUTHOR") "CERN DEM JLC")
      )
      (libsource (lib "Resistors") (part "Resistor"))
    )
    (comp (ref "R229")
      (value "0")
      (footprint "RESC1005X40N")
      (description "Resistor")
      (fields
        (field (name "PART NUMBER") "R0402_0R_JUMPER")
        (field (name "MANUFACTURER") "GENERIC")
        (field (name "AUTHOR") "CERN DEM JLC")
      )
      (libsource (lib "Resistors") (part "Resistor"))
    )
    (comp (ref "R230")
      (value "0")
      (footprint "RESC1005X40N")
      (description "Resistor")
      (fields
        (field (name "PART NUMBER") "R0402_0R_JUMPER")
        (field (name "MANUFACTURER") "GENERIC")
        (field (name "AUTHOR") "CERN DEM JLC")
      )
      (libsource (lib "Resistors") (part "Resistor"))
    )
    (comp (ref "R231")
      (value "162k")
      (footprint "RESC1005X40N")
      (description "Resistor - 1%")
      (fields
        (field (name "TOLERANCE") "±1%")
        (field (name "PART NUMBER") "R0402_162K_1%_0.063W_100PPM")
        (field (name "POWER") "0.063W")
        (field (name "AUTHOR") "CERN DEM BC")
      )
      (libsource (lib "") (part "Resistor - 1%_1"))
    )
    (comp (ref "T3")
      (value "SI4425DDY-T1-GE3")
      (footprint "SOIC127P600X175-8N")
      (description "-30V -19.7A P-Channel MOSFET")
      (fields (field (name "MANUFACTURER") "VISHAY SILICONIX") (field (name "AUTHOR") "CERN DEM MR"))
      (libsource (lib "ICs And Semiconductors") (part "SI4425DDY"))
    )
    (comp (ref "T4")
      (value "FDN86246")
      (footprint "SOT95P237X112-3N")
      (description "N-CHANNEL MOSFET WITH DIODE")
      (fields (field (name "MANUFACTURER") "ON SEMICONDUCTOR") (field (name "AUTHOR") "CERN DEM BC"))
      (libsource (lib "ICs And Semiconductors") (part "N-MOSFET-D 1G 2S 3D"))
    )
    (comp (ref "T5")
      (value "BC857BV")
      (footprint "SOTFL50P160X60-6N")
      (description "45V, 100mA PNP General Purpose Double Transistor")
      (fields (field (name "MANUFACTURER") "NXP SEMICONDUCTORS") (field (name "AUTHOR") "CERN DEM JLC"))
      (libsource (lib "ICs And Semiconductors") (part "BC857BV"))
    )
    (comp (ref "T6")
      (value "BSS138LT1G")
      (footprint "SOT95P240X110-3N")
      (description "N-CHANNEL MOSFET WITH DIODE")
      (fields (field (name "MANUFACTURER") "ON SEMICONDUCTOR") (field (name "AUTHOR") "CERN DEM JLC"))
      (libsource (lib "") (part "N-MOSFET-D 1G 2S 3D_1"))
    )
    (comp (ref "T7")
      (value "BSS84AK")
      (footprint "SOT95P230X110-3N")
      (description "50V, 180mA P-Channel Trench MOSFET")
      (fields (field (name "MANUFACTURER") "NXP SEMICONDUCTORS") (field (name "AUTHOR") "CERN DEM JLC"))
      (libsource (lib "ICs And Semiconductors") (part "BSS84"))
    )
    (comp (ref "T8")
      (value "BSS138LT1G")
      (footprint "SOT95P240X110-3N")
      (description "N-CHANNEL MOSFET WITH DIODE")
      (fields (field (name "MANUFACTURER") "ON SEMICONDUCTOR") (field (name "AUTHOR") "CERN DEM JLC"))
      (libsource (lib "ICs And Semiconductors") (part "N-MOSFET-D 1G 2S 3D"))
    )
    (comp (ref "TP4")
      (value "SMD Pad")
      (footprint "C60")
      (description "Test Point")
      (fields (field (name "PART NUMBER") "SMD_PAD_D0.6MM") (field (name "AUTHOR") "CERN DEM HF"))
      (libsource (lib "Eletro-mechanical") (part "Test Point"))
    )
    (comp (ref "TP5")
      (value "SMD Pad")
      (footprint "C60")
      (description "Test Point")
      (fields (field (name "PART NUMBER") "SMD_PAD_D0.6MM") (field (name "AUTHOR") "CERN DEM HF"))
      (libsource (lib "Eletro-mechanical") (part "Test Point"))
    )
    (comp (ref "TP6")
      (value "Test Point")
      (footprint "TPS127")
      (fields (field (name "PART NUMBER") "SMD_PAD_1.27X1.27MM") (field (name "AUTHOR") "CERN DEM JLC"))
      (libsource (lib "Eletro-mechanical") (part "Test Point"))
    )
    (comp (ref "TP7")
      (value "Test Point")
      (footprint "TPS127")
      (fields (field (name "PART NUMBER") "SMD_PAD_1.27X1.27MM") (field (name "AUTHOR") "CERN DEM JLC"))
      (libsource (lib "Eletro-mechanical") (part "Test Point"))
    )
    (comp (ref "TP8")
      (value "Test Point")
      (footprint "TPS127")
      (fields (field (name "PART NUMBER") "SMD_PAD_1.27X1.27MM") (field (name "AUTHOR") "CERN DEM JLC"))
      (libsource (lib "Eletro-mechanical") (part "Test Point"))
    )
    (comp (ref "TP9")
      (value "Test Point")
      (footprint "TPS127")
      (fields (field (name "PART NUMBER") "SMD_PAD_1.27X1.27MM") (field (name "AUTHOR") "CERN DEM JLC"))
      (libsource (lib "Eletro-mechanical") (part "Test Point"))
    )
    (comp (ref "TP10")
      (value "Test Point")
      (footprint "TPS127")
      (fields (field (name "PART NUMBER") "SMD_PAD_1.27X1.27MM") (field (name "AUTHOR") "CERN DEM JLC"))
      (libsource (lib "Eletro-mechanical") (part "Test Point"))
    )
    (comp (ref "TP11")
      (value "Test Point")
      (footprint "TPS127")
      (fields (field (name "PART NUMBER") "SMD_PAD_1.27X1.27MM") (field (name "AUTHOR") "CERN DEM JLC"))
      (libsource (lib "Eletro-mechanical") (part "Test Point"))
    )
    (comp (ref "TP12")
      (value "SMD Pad")
      (footprint "C60")
      (description "Test Point")
      (fields (field (name "PART NUMBER") "SMD_PAD_D0.6MM") (field (name "AUTHOR") "CERN DEM HF"))
      (libsource (lib "Eletro-mechanical") (part "Test Point"))
    )
    (comp (ref "TP13")
      (value "SMD Pad")
      (footprint "C60")
      (description "Test Point")
      (fields (field (name "PART NUMBER") "SMD_PAD_D0.6MM") (field (name "AUTHOR") "CERN DEM HF"))
      (libsource (lib "Eletro-mechanical") (part "Test Point"))
    )
    (comp (ref "TP14")
      (value "SMD Pad")
      (footprint "C60")
      (description "Test Point")
      (fields (field (name "PART NUMBER") "SMD_PAD_D0.6MM") (field (name "AUTHOR") "CERN DEM HF"))
      (libsource (lib "Eletro-mechanical") (part "Test Point"))
    )
  )
  (nets
    (net (code "1") (name "/AT_EVENT") (class "Default")
      (node (ref "IC6") (pin "4") (pinfunction "C_4") (pintype "open_collector"))
      (node (ref "R67") (pin "1") (pinfunction "1_1") (pintype "passive"))
    )
    (net (code "2") (name "/CPU_RESETn") (class "Default")
      (node (ref "T6") (pin "1") (pinfunction "G_1") (pintype "passive"))
    )
    (net (code "3") (name "/FAN_PWM") (class "Default")
      (node (ref "C82") (pin "1") (pinfunction "1_1") (pintype "passive"))
    )
    (net (code "4") (name "/I_meas_P12V0") (class "Default")
      (node (ref "C89") (pin "1") (pinfunction "1_1") (pintype "passive"))
      (node (ref "R141") (pin "2") (pinfunction "2_2") (pintype "passive"))
    )
    (net (code "5") (name "/P12V0_POE") (class "Default")
      (node (ref "C3") (pin "1") (pinfunction "1_1") (pintype "passive"))
      (node (ref "C4") (pin "1") (pinfunction "1_1") (pintype "passive"))
      (node (ref "IC3") (pin "8") (pinfunction "+VDC_8") (pintype "input"))
      (node (ref "R30") (pin "2") (pinfunction "2_2") (pintype "passive"))
      (node (ref "T3") (pin "5") (pinfunction "D_5") (pintype "passive"))
      (node (ref "T3") (pin "6") (pinfunction "D_6") (pintype "passive"))
      (node (ref "T3") (pin "7") (pinfunction "D_7") (pintype "passive"))
      (node (ref "T3") (pin "8") (pinfunction "D_8") (pintype "passive"))
      (node (ref "T5") (pin "4") (pinfunction "E_4") (pintype "passive"))
    )
    (net (code "6") (name "/POE_PWR_SRC") (class "Default")
      (node (ref "R30") (pin "1") (pinfunction "1_1") (pintype "passive"))
      (node (ref "R31") (pin "2") (pinfunction "2_2") (pintype "passive"))
    )
    (net (code "7") (name "/POE_VC+") (class "Default")
      (node (ref "L1") (pin "1") (pinfunction "1_1") (pintype "passive"))
      (node (ref "R14") (pin "2") (pinfunction "2_2") (pintype "passive"))
    )
    (net (code "8") (name "/POE_VC-") (class "Default")
      (node (ref "R35") (pin "1") (pinfunction "1_1") (pintype "passive"))
      (node (ref "R64") (pin "1") (pinfunction "1_1") (pintype "passive"))
      (node (ref "R66") (pin "1") (pinfunction "1_1") (pintype "passive"))
      (node (ref "T4") (pin "2") (pinfunction "S_2") (pintype "passive"))
    )
    (net (code "9") (name "/TACHO") (class "Default")
      (node (ref "R9") (pin "1") (pinfunction "1_1") (pintype "passive"))
    )
    (net (code "10") (name "/clkoutA") (class "Default")
      (node (ref "B20") (pin "1") (pinfunction "1_1") (pintype "bidirectional"))
      (node (ref "IC34") (pin "B5") (pinfunction "CLKOUT_B5") (pintype "output"))
      (node (ref "IC35") (pin "A5") (pinfunction "CLKIN_A5") (pintype "input"))
    )
    (net (code "11") (name "/clkoutB") (class "Default")
      (node (ref "B21") (pin "1") (pinfunction "1_1") (pintype "bidirectional"))
      (node (ref "IC35") (pin "B5") (pinfunction "CLKOUT_B5") (pintype "output"))
      (node (ref "IC37") (pin "A5") (pinfunction "CLKIN_A5") (pintype "input"))
    )
    (net (code "12") (name "GND") (class "Default")
      (node (ref "B25") (pin "1") (pinfunction "1_1") (pintype "bidirectional"))
      (node (ref "C10") (pin "1") (pinfunction "1_1") (pintype "passive"))
      (node (ref "C101") (pin "1") (pinfunction "1_1") (pintype "passive"))
      (node (ref "C11") (pin "1") (pinfunction "1_1") (pintype "passive"))
      (node (ref "C112") (pin "2") (pinfunction "2_2") (pintype "passive"))
      (node (ref "C113") (pin "1") (pinfunction "1_1") (pintype "passive"))
      (node (ref "C114") (pin "2") (pinfunction "2_2") (pintype "passive"))
      (node (ref "C115") (pin "1") (pinfunction "1_1") (pintype "passive"))
      (node (ref "C117") (pin "1") (pinfunction "1_1") (pintype "passive"))
      (node (ref "C12") (pin "1") (pinfunction "1_1") (pintype "passive"))
      (node (ref "C13") (pin "1") (pinfunction "1_1") (pintype "passive"))
      (node (ref "C14") (pin "1") (pinfunction "1_1") (pintype "passive"))
      (node (ref "C15") (pin "2") (pinfunction "2_2") (pintype "passive"))
      (node (ref "C152") (pin "1") (pinfunction "1_1") (pintype "passive"))
      (node (ref "C155") (pin "1") (pinfunction "1_1") (pintype "passive"))
      (node (ref "C156") (pin "1") (pinfunction "1_1") (pintype "passive"))
      (node (ref "C157") (pin "1") (pinfunction "1_1") (pintype "passive"))
      (node (ref "C158") (pin "1") (pinfunction "1_1") (pintype "passive"))
      (node (ref "C159") (pin "2") (pinfunction "2_2") (pintype "passive"))
      (node (ref "C163") (pin "1") (pinfunction "1_1") (pintype "passive"))
      (node (ref "C164") (pin "1") (pinfunction "1_1") (pintype "passive"))
      (node (ref "C165") (pin "2") (pinfunction "2_2") (pintype "passive"))
      (node (ref "C166") (pin "1") (pinfunction "1_1") (pintype "passive"))
      (node (ref "C167") (pin "1") (pinfunction "1_1") (pintype "passive"))
      (node (ref "C19") (pin "2") (pinfunction "2_2") (pintype "passive"))
      (node (ref "C3") (pin "2") (pinfunction "2_2") (pintype "passive"))
      (node (ref "C34") (pin "1") (pinfunction "1_1") (pintype "passive"))
      (node (ref "C37") (pin "2") (pinfunction "2_2") (pintype "passive"))
      (node (ref "C38") (pin "2") (pinfunction "2_2") (pintype "passive"))
      (node (ref "C4") (pin "2") (pinfunction "2_2") (pintype "passive"))
      (node (ref "C6") (pin "1") (pinfunction "1_1") (pintype "passive"))
      (node (ref "C7") (pin "1") (pinfunction "1_1") (pintype "passive"))
      (node (ref "C78") (pin "1") (pinfunction "1_1") (pintype "passive"))
      (node (ref "C8") (pin "1") (pinfunction "1_1") (pintype "passive"))
      (node (ref "C89") (pin "2") (pinfunction "2_2") (pintype "passive"))
      (node (ref "C9") (pin "1") (pinfunction "1_1") (pintype "passive"))
      (node (ref "C91") (pin "2") (pinfunction "2_2") (pintype "passive"))
      (node (ref "D12") (pin "2") (pinfunction "A_2") (pintype "passive"))
      (node (ref "D24") (pin "2") (pinfunction "A_2") (pintype "passive"))
      (node (ref "D25") (pin "2") (pinfunction "A_2") (pintype "passive"))
      (node (ref "IC12") (pin "2") (pinfunction "GND_2") (pintype "power_in"))
      (node (ref "IC15") (pin "1") (pinfunction "GND_1") (pintype "power_in"))
      (node (ref "IC15") (pin "5") (pinfunction "PGND_5") (pintype "power_in"))
      (node (ref "IC15") (pin "56") (pinfunction "GND_56") (pintype "power_in"))
      (node (ref "IC15") (pin "64") (pinfunction "GND_64") (pintype "power_in"))
      (node (ref "IC15") (pin "65") (pinfunction "EPAD_65") (pintype "power_in"))
      (node (ref "IC16") (pin "4") (pinfunction "GND_4") (pintype "power_in"))
      (node (ref "IC17") (pin "2") (pinfunction "GND_2") (pintype "power_in"))
      (node (ref "IC18") (pin "3") (pinfunction "GND_3") (pintype "power_in"))
      (node (ref "IC18") (pin "6") (pinfunction "GND_6") (pintype "power_in"))
      (node (ref "IC18") (pin "9") (pinfunction "EP_9") (pintype "power_in"))
      (node (ref "IC22") (pin "2") (pinfunction "GND_2") (pintype "power_in"))
      (node (ref "IC3") (pin "10") (pinfunction "-VDC_10") (pintype "power_in"))
      (node (ref "IC3") (pin "7") (pinfunction "-VDC_7") (pintype "power_in"))
      (node (ref "IC34") (pin "B3") (pinfunction "GND_B3") (pintype "power_in"))
      (node (ref "IC34") (pin "B4") (pinfunction "SGND_B4") (pintype "power_in"))
      (node (ref "IC34") (pin "C3") (pinfunction "GND_C3") (pintype "power_in"))
      (node (ref "IC34") (pin "D3") (pinfunction "GND_D3") (pintype "power_in"))
      (node (ref "IC34") (pin "D4") (pinfunction "GND_D4") (pintype "power_in"))
      (node (ref "IC34") (pin "E3") (pinfunction "GND_E3") (pintype "power_in"))
      (node (ref "IC35") (pin "B3") (pinfunction "GND_B3") (pintype "power_in"))
      (node (ref "IC35") (pin "B4") (pinfunction "SGND_B4") (pintype "power_in"))
      (node (ref "IC35") (pin "C3") (pinfunction "GND_C3") (pintype "power_in"))
      (node (ref "IC35") (pin "D3") (pinfunction "GND_D3") (pintype "power_in"))
      (node (ref "IC35") (pin "D4") (pinfunction "GND_D4") (pintype "power_in"))
      (node (ref "IC35") (pin "E3") (pinfunction "GND_E3") (pintype "power_in"))
      (node (ref "IC37") (pin "B3") (pinfunction "GND_B3") (pintype "power_in"))
      (node (ref "IC37") (pin "B4") (pinfunction "SGND_B4") (pintype "power_in"))
      (node (ref "IC37") (pin "C3") (pinfunction "GND_C3") (pintype "power_in"))
      (node (ref "IC37") (pin "D3") (pinfunction "GND_D3") (pintype "power_in"))
      (node (ref "IC37") (pin "D4") (pinfunction "GND_D4") (pintype "power_in"))
      (node (ref "IC37") (pin "E3") (pinfunction "GND_E3") (pintype "power_in"))
      (node (ref "IC6") (pin "3") (pinfunction "E_3") (pintype "open_emitter"))
      (node (ref "J4") (pin "1") (pinfunction "1_1") (pintype "bidirectional"))
      (node (ref "J5") (pin "1") (pinfunction "1_1") (pintype "bidirectional"))
      (node (ref "J5") (pin "2") (pinfunction "2_2") (pintype "bidirectional"))
      (node (ref "J6") (pin "1") (pinfunction "1_1") (pintype "bidirectional"))
      (node (ref "LD10") (pin "1") (pinfunction "C_1") (pintype "passive"))
      (node (ref "LD2") (pin "1") (pinfunction "C_1") (pintype "passive"))
      (node (ref "LD3") (pin "1") (pinfunction "C_1") (pintype "passive"))
      (node (ref "LD4") (pin "1") (pinfunction "C_1") (pintype "passive"))
      (node (ref "LD6") (pin "1") (pinfunction "C_1") (pintype "passive"))
      (node (ref "LD9") (pin "1") (pinfunction "C_1") (pintype "passive"))
      (node (ref "R104") (pin "1") (pinfunction "1_1") (pintype "passive"))
      (node (ref "R139") (pin "1") (pinfunction "1_1") (pintype "passive"))
      (node (ref "R154") (pin "1") (pinfunction "1_1") (pintype "passive"))
      (node (ref "R219") (pin "1") (pinfunction "1_1") (pintype "passive"))
      (node (ref "R221") (pin "1") (pinfunction "1_1") (pintype "passive"))
      (node (ref "R222") (pin "1") (pinfunction "1_1") (pintype "passive"))
      (node (ref "R228") (pin "1") (pinfunction "1_1") (pintype "passive"))
      (node (ref "R230") (pin "1") (pinfunction "1_1") (pintype "passive"))
      (node (ref "R231") (pin "1") (pinfunction "1_1") (pintype "passive"))
      (node (ref "R31") (pin "1") (pinfunction "1_1") (pintype "passive"))
      (node (ref "R68") (pin "1") (pinfunction "1_1") (pintype "passive"))
      (node (ref "R85") (pin "1") (pinfunction "1_1") (pintype "passive"))
      (node (ref "T6") (pin "2") (pinfunction "S_2") (pintype "passive"))
      (node (ref "T8") (pin "2") (pinfunction "S_2") (pintype "passive"))
      (node (ref "TP9") (pin "1") (pinfunction "1_1") (pintype "bidirectional"))
    )
    (net (code "13") (name "Net-(C5-Pad2)") (class "Default")
      (node (ref "C5") (pin "2") (pinfunction "2_2") (pintype "passive"))
      (node (ref "L1") (pin "2") (pinfunction "2_2") (pintype "passive"))
      (node (ref "L6") (pin "1") (pinfunction "1_1") (pintype "passive"))
    )
    (net (code "14") (name "Net-(C27-Pad2)") (class "Default")
      (node (ref "C27") (pin "2") (pinfunction "2_2") (pintype "passive"))
      (node (ref "R96") (pin "2") (pinfunction "2_2") (pintype "passive"))
    )
    (net (code "15") (name "Net-(C152-Pad2)") (class "Default")
      (node (ref "C152") (pin "2") (pinfunction "2_2") (pintype "passive"))
      (node (ref "IC15") (pin "2") (pinfunction "PVDD_2") (pintype "power_in"))
      (node (ref "IC15") (pin "3") (pinfunction "PVDD_3") (pintype "power_in"))
      (node (ref "IC15") (pin "49") (pinfunction "ANODE_49") (pintype "passive"))
      (node (ref "IC15") (pin "50") (pinfunction "ANODE_50") (pintype "passive"))
      (node (ref "IC15") (pin "62") (pinfunction "5VDD_62") (pintype "power_in"))
      (node (ref "IC15") (pin "63") (pinfunction "5VDD_63") (pintype "power_in"))
    )
    (net (code "16") (name "Net-(D12-C)") (class "Default")
      (node (ref "D12") (pin "1") (pinfunction "C_1") (pintype "passive"))
      (node (ref "J6") (pin "2") (pinfunction "2_2") (pintype "bidirectional"))
      (node (ref "T7") (pin "3") (pinfunction "D_3") (pintype "passive"))
    )
    (net (code "17") (name "Net-(D28-A)") (class "Default")
      (node (ref "C82") (pin "2") (pinfunction "2_2") (pintype "passive"))
      (node (ref "D28") (pin "2") (pinfunction "A_2") (pintype "passive"))
      (node (ref "R121") (pin "1") (pinfunction "1_1") (pintype "passive"))
      (node (ref "T8") (pin "1") (pinfunction "G_1") (pintype "passive"))
    )
    (net (code "18") (name "Net-(IC3-AT-DET)") (class "Default")
      (node (ref "IC3") (pin "3") (pinfunction "AT-DET_3") (pintype "input"))
      (node (ref "IC6") (pin "2") (pinfunction "C_2") (pintype "input"))
    )
    (net (code "19") (name "Net-(IC3-VIN+)") (class "Default")
      (node (ref "C6") (pin "2") (pinfunction "2_2") (pintype "passive"))
      (node (ref "IC3") (pin "1") (pinfunction "VIN+_1") (pintype "input"))
      (node (ref "IC6") (pin "1") (pinfunction "A_1") (pintype "input"))
      (node (ref "L6") (pin "4") (pinfunction "4_4") (pintype "passive"))
    )
    (net (code "20") (name "Net-(IC3-VIN-)") (class "Default")
      (node (ref "C7") (pin "2") (pinfunction "2_2") (pintype "passive"))
      (node (ref "IC3") (pin "2") (pinfunction "VIN-_2") (pintype "output"))
      (node (ref "L6") (pin "3") (pinfunction "3_3") (pintype "passive"))
    )
    (net (code "21") (name "Net-(IC4-A)") (class "Default")
      (node (ref "IC4") (pin "1") (pinfunction "A_1") (pintype "input"))
      (node (ref "R16") (pin "1") (pinfunction "1_1") (pintype "passive"))
    )
    (net (code "22") (name "Net-(IC4-C-Pad4)") (class "Default")
      (node (ref "IC4") (pin "4") (pinfunction "C_4") (pintype "open_collector"))
      (node (ref "R14") (pin "1") (pinfunction "1_1") (pintype "passive"))
      (node (ref "R35") (pin "2") (pinfunction "2_2") (pintype "passive"))
    )
    (net (code "23") (name "Net-(IC4-E)") (class "Default")
      (node (ref "IC4") (pin "3") (pinfunction "E_3") (pintype "open_emitter"))
      (node (ref "R66") (pin "2") (pinfunction "2_2") (pintype "passive"))
      (node (ref "T4") (pin "1") (pinfunction "G_1") (pintype "passive"))
    )
    (net (code "24") (name "Net-(IC12-VIN)") (class "Default")
      (node (ref "C114") (pin "1") (pinfunction "1_1") (pintype "passive"))
      (node (ref "IC12") (pin "1") (pinfunction "VIN_1") (pintype "input"))
      (node (ref "R124") (pin "2") (pinfunction "2_2") (pintype "passive"))
    )
    (net (code "25") (name "Net-(IC15-EN)") (class "Default")
      (node (ref "IC15") (pin "59") (pinfunction "EN_59") (pintype "passive"))
      (node (ref "R138") (pin "2") (pinfunction "2_2") (pintype "passive"))
    )
    (net (code "26") (name "Net-(IC15-FB)") (class "Default")
      (node (ref "C118") (pin "1") (pinfunction "1_1") (pintype "passive"))
      (node (ref "IC15") (pin "48") (pinfunction "RIB_48") (pintype "passive"))
      (node (ref "IC15") (pin "57") (pinfunction "FB_57") (pintype "input"))
      (node (ref "R86") (pin "1") (pinfunction "1_1") (pintype "passive"))
      (node (ref "R89") (pin "2") (pinfunction "2_2") (pintype "passive"))
    )
    (net (code "27") (name "Net-(IC15-FREQ)") (class "Default")
      (node (ref "IC15") (pin "61") (pinfunction "FREQ_61") (pintype "passive"))
      (node (ref "R128") (pin "2") (pinfunction "2_2") (pintype "passive"))
    )
    (net (code "28") (name "Net-(IC15-ILIM)") (class "Default")
      (node (ref "C34") (pin "2") (pinfunction "2_2") (pintype "passive"))
      (node (ref "IC15") (pin "4") (pinfunction "ILIM_4") (pintype "passive"))
      (node (ref "R95") (pin "1") (pinfunction "1_1") (pintype "passive"))
    )
    (net (code "29") (name "Net-(IC15-SW-Pad10)") (class "Default")
      (node (ref "IC15") (pin "10") (pinfunction "SW_10") (pintype "passive"))
      (node (ref "IC15") (pin "38") (pinfunction "SW_38") (pintype "passive"))
      (node (ref "IC15") (pin "39") (pinfunction "SW_39") (pintype "passive"))
      (node (ref "IC15") (pin "40") (pinfunction "SW_40") (pintype "passive"))
      (node (ref "IC15") (pin "41") (pinfunction "SW_41") (pintype "passive"))
      (node (ref "IC15") (pin "42") (pinfunction "SW_42") (pintype "passive"))
      (node (ref "IC15") (pin "43") (pinfunction "SW_43") (pintype "passive"))
      (node (ref "IC15") (pin "44") (pinfunction "SW_44") (pintype "passive"))
      (node (ref "IC15") (pin "7") (pinfunction "SW_7") (pintype "passive"))
      (node (ref "IC15") (pin "8") (pinfunction "SW_8") (pintype "passive"))
      (node (ref "IC15") (pin "9") (pinfunction "SW_9") (pintype "passive"))
      (node (ref "R95") (pin "2") (pinfunction "2_2") (pintype "passive"))
    )
    (net (code "30") (name "Net-(IC16-COMP)") (class "Default")
      (node (ref "IC16") (pin "7") (pinfunction "COMP_7") (pintype "input"))
      (node (ref "R96") (pin "1") (pinfunction "1_1") (pintype "passive"))
    )
    (net (code "31") (name "Net-(IC16-IN)") (class "Default")
      (node (ref "C19") (pin "1") (pinfunction "1_1") (pintype "passive"))
      (node (ref "C37") (pin "1") (pinfunction "1_1") (pintype "passive"))
      (node (ref "IC16") (pin "2") (pinfunction "IN_2") (pintype "input"))
      (node (ref "R97") (pin "2") (pinfunction "2_2") (pintype "passive"))
    )
    (net (code "32") (name "Net-(IC17-FB)") (class "Default")
      (node (ref "IC17") (pin "5") (pinfunction "FB_5") (pintype "input"))
      (node (ref "R102") (pin "1") (pinfunction "1_1") (pintype "passive"))
      (node (ref "R103") (pin "2") (pinfunction "2_2") (pintype "passive"))
    )
    (net (code "33") (name "Net-(IC17-SW)") (class "Default")
      (node (ref "IC17") (pin "3") (pinfunction "SW_3") (pintype "power_in"))
      (node (ref "L8") (pin "1") (pinfunction "1_1") (pintype "passive"))
    )
    (net (code "34") (name "Net-(IC18-VIN)") (class "Default")
      (node (ref "C112") (pin "1") (pinfunction "1_1") (pintype "passive"))
      (node (ref "IC18") (pin "8") (pinfunction "VIN_8") (pintype "input"))
      (node (ref "R105") (pin "2") (pinfunction "2_2") (pintype "passive"))
    )
    (net (code "35") (name "Net-(IC22-OUT)") (class "Default")
      (node (ref "IC22") (pin "1") (pinfunction "OUT_1") (pintype "output"))
      (node (ref "R141") (pin "1") (pinfunction "1_1") (pintype "passive"))
      (node (ref "R154") (pin "2") (pinfunction "2_2") (pintype "passive"))
    )
    (net (code "36") (name "Net-(IC22-VIN-)") (class "Default")
      (node (ref "IC22") (pin "3") (pinfunction "VIN-_3") (pintype "input"))
      (node (ref "R131") (pin "1") (pinfunction "1_1") (pintype "passive"))
    )
    (net (code "37") (name "Net-(IC34-COMP)") (class "Default")
      (node (ref "IC34") (pin "A1") (pinfunction "COMP_A1") (pintype "input"))
      (node (ref "IC35") (pin "A1") (pinfunction "COMP_A1") (pintype "input"))
      (node (ref "IC37") (pin "A1") (pinfunction "COMP_A1") (pintype "input"))
    )
    (net (code "38") (name "Net-(IC34-FB)") (class "Default")
      (node (ref "IC34") (pin "B1") (pinfunction "FB_B1") (pintype "input"))
      (node (ref "IC35") (pin "B1") (pinfunction "FB_B1") (pintype "input"))
      (node (ref "IC37") (pin "B1") (pinfunction "FB_B1") (pintype "input"))
      (node (ref "R222") (pin "2") (pinfunction "2_2") (pintype "passive"))
    )
    (net (code "39") (name "Net-(IC34-FREQ)") (class "Default")
      (node (ref "IC34") (pin "A4") (pinfunction "FREQ_A4") (pintype "input"))
      (node (ref "R219") (pin "2") (pinfunction "2_2") (pintype "passive"))
    )
    (net (code "40") (name "Net-(IC34-INTVCC)") (class "Default")
      (node (ref "IC34") (pin "C4") (pinfunction "MODE_C4") (pintype "input"))
      (node (ref "IC34") (pin "E4") (pinfunction "INTVCC_E4") (pintype "power_in"))
      (node (ref "R227") (pin "2") (pinfunction "2_2") (pintype "passive"))
    )
    (net (code "41") (name "Net-(IC34-PGOOD)") (class "Default")
      (node (ref "B10") (pin "1") (pinfunction "1_1") (pintype "bidirectional"))
      (node (ref "IC34") (pin "C2") (pinfunction "PGOOD_C2") (pintype "open_collector"))
    )
    (net (code "42") (name "Net-(IC34-PHMODE)") (class "Default")
      (node (ref "IC34") (pin "B2") (pinfunction "PHMODE_B2") (pintype "input"))
      (node (ref "R227") (pin "1") (pinfunction "1_1") (pintype "passive"))
      (node (ref "R228") (pin "2") (pinfunction "2_2") (pintype "passive"))
    )
    (net (code "43") (name "Net-(IC34-TRACK{slash}SS)") (class "Default")
      (node (ref "C159") (pin "1") (pinfunction "1_1") (pintype "passive"))
      (node (ref "IC34") (pin "A2") (pinfunction "TRACK/SS_A2") (pintype "input"))
      (node (ref "IC35") (pin "A2") (pinfunction "TRACK/SS_A2") (pintype "input"))
      (node (ref "IC37") (pin "A2") (pinfunction "TRACK/SS_A2") (pintype "input"))
    )
    (net (code "44") (name "Net-(IC35-FREQ)") (class "Default")
      (node (ref "IC35") (pin "A4") (pinfunction "FREQ_A4") (pintype "input"))
      (node (ref "R221") (pin "2") (pinfunction "2_2") (pintype "passive"))
    )
    (net (code "45") (name "Net-(IC35-INTVCC)") (class "Default")
      (node (ref "IC35") (pin "C4") (pinfunction "MODE_C4") (pintype "input"))
      (node (ref "IC35") (pin "E4") (pinfunction "INTVCC_E4") (pintype "power_in"))
      (node (ref "R229") (pin "2") (pinfunction "2_2") (pintype "passive"))
    )
    (net (code "46") (name "Net-(IC35-PGOOD)") (class "Default")
      (node (ref "B19") (pin "1") (pinfunction "1_1") (pintype "bidirectional"))
      (node (ref "IC35") (pin "C2") (pinfunction "PGOOD_C2") (pintype "open_collector"))
    )
    (net (code "47") (name "Net-(IC35-PHMODE)") (class "Default")
      (node (ref "IC35") (pin "B2") (pinfunction "PHMODE_B2") (pintype "input"))
      (node (ref "R229") (pin "1") (pinfunction "1_1") (pintype "passive"))
      (node (ref "R230") (pin "2") (pinfunction "2_2") (pintype "passive"))
    )
    (net (code "48") (name "Net-(IC37-FREQ)") (class "Default")
      (node (ref "IC37") (pin "A4") (pinfunction "FREQ_A4") (pintype "input"))
      (node (ref "R231") (pin "2") (pinfunction "2_2") (pintype "passive"))
    )
    (net (code "49") (name "Net-(IC37-INTVCC)") (class "Default")
      (node (ref "IC37") (pin "C4") (pinfunction "MODE_C4") (pintype "input"))
      (node (ref "IC37") (pin "E4") (pinfunction "INTVCC_E4") (pintype "power_in"))
    )
    (net (code "50") (name "Net-(IC37-PGOOD)") (class "Default")
      (node (ref "B18") (pin "1") (pinfunction "1_1") (pintype "bidirectional"))
      (node (ref "IC37") (pin "C2") (pinfunction "PGOOD_C2") (pintype "open_collector"))
    )
    (net (code "51") (name "Net-(J6-Pad3)") (class "Default")
      (node (ref "J6") (pin "3") (pinfunction "3_3") (pintype "bidirectional"))
      (node (ref "R101") (pin "2") (pinfunction "2_2") (pintype "passive"))
      (node (ref "R9") (pin "2") (pinfunction "2_2") (pintype "passive"))
    )
    (net (code "52") (name "Net-(LD2-A)") (class "Default")
      (node (ref "LD2") (pin "2") (pinfunction "A_2") (pintype "passive"))
      (node (ref "R90") (pin "1") (pinfunction "1_1") (pintype "passive"))
    )
    (net (code "53") (name "Net-(LD3-A)") (class "Default")
      (node (ref "LD3") (pin "2") (pinfunction "A_2") (pintype "passive"))
      (node (ref "R94") (pin "2") (pinfunction "2_2") (pintype "passive"))
    )
    (net (code "54") (name "Net-(LD4-A)") (class "Default")
      (node (ref "LD4") (pin "2") (pinfunction "A_2") (pintype "passive"))
      (node (ref "R100") (pin "2") (pinfunction "2_2") (pintype "passive"))
    )
    (net (code "55") (name "Net-(LD6-A)") (class "Default")
      (node (ref "LD6") (pin "2") (pinfunction "A_2") (pintype "passive"))
      (node (ref "R10") (pin "2") (pinfunction "2_2") (pintype "passive"))
    )
    (net (code "56") (name "Net-(LD9-A)") (class "Default")
      (node (ref "LD9") (pin "2") (pinfunction "A_2") (pintype "passive"))
      (node (ref "R39") (pin "2") (pinfunction "2_2") (pintype "passive"))
    )
    (net (code "57") (name "Net-(LD10-A)") (class "Default")
      (node (ref "LD10") (pin "2") (pinfunction "A_2") (pintype "passive"))
      (node (ref "R54") (pin "2") (pinfunction "2_2") (pintype "passive"))
    )
    (net (code "58") (name "Net-(R103-Pad1)") (class "Default")
      (node (ref "R103") (pin "1") (pinfunction "1_1") (pintype "passive"))
      (node (ref "R104") (pin "2") (pinfunction "2_2") (pintype "passive"))
    )
    (net (code "59") (name "Net-(R105-Pad1)") (class "Default")
      (node (ref "R105") (pin "1") (pinfunction "1_1") (pintype "passive"))
      (node (ref "R88") (pin "2") (pinfunction "2_2") (pintype "passive"))
    )
    (net (code "60") (name "Net-(R139-Pad2)") (class "Default")
      (node (ref "R139") (pin "2") (pinfunction "2_2") (pintype "passive"))
      (node (ref "R89") (pin "1") (pinfunction "1_1") (pintype "passive"))
    )
    (net (code "61") (name "Net-(T4-D)") (class "Default")
      (node (ref "C5") (pin "1") (pinfunction "1_1") (pintype "passive"))
      (node (ref "L6") (pin "2") (pinfunction "2_2") (pintype "passive"))
      (node (ref "R64") (pin "2") (pinfunction "2_2") (pintype "passive"))
      (node (ref "T4") (pin "3") (pinfunction "D_3") (pintype "passive"))
    )
    (net (code "62") (name "Net-(T5A-B)") (class "Default")
      (node (ref "R65") (pin "1") (pinfunction "1_1") (pintype "passive"))
      (node (ref "T5") (pin "2") (pinfunction "B_2") (pintype "passive"))
    )
    (net (code "63") (name "Net-(T5A-C)") (class "Default")
      (node (ref "R68") (pin "2") (pinfunction "2_2") (pintype "passive"))
      (node (ref "T3") (pin "4") (pinfunction "S_4") (pintype "passive"))
      (node (ref "T5") (pin "6") (pinfunction "C_6") (pintype "passive"))
    )
    (net (code "64") (name "Net-(T5B-B)") (class "Default")
      (node (ref "R65") (pin "2") (pinfunction "2_2") (pintype "passive"))
      (node (ref "R85") (pin "2") (pinfunction "2_2") (pintype "passive"))
      (node (ref "T5") (pin "3") (pinfunction "C_3") (pintype "passive"))
      (node (ref "T5") (pin "5") (pinfunction "B_5") (pintype "passive"))
    )
    (net (code "65") (name "Net-(T6-D)") (class "Default")
      (node (ref "IC4") (pin "2") (pinfunction "C_2") (pintype "input"))
      (node (ref "T6") (pin "3") (pinfunction "D_3") (pintype "passive"))
    )
    (net (code "66") (name "Net-(T7-G)") (class "Default")
      (node (ref "R13") (pin "1") (pinfunction "1_1") (pintype "passive"))
      (node (ref "T7") (pin "1") (pinfunction "G_1") (pintype "passive"))
      (node (ref "T8") (pin "3") (pinfunction "D_3") (pintype "passive"))
    )
    (net (code "67") (name "P3V0REF") (class "Default")
      (node (ref "C27") (pin "1") (pinfunction "1_1") (pintype "passive"))
      (node (ref "C38") (pin "1") (pinfunction "1_1") (pintype "passive"))
      (node (ref "IC16") (pin "6") (pinfunction "OUT_6") (pintype "power_in"))
      (node (ref "R54") (pin "1") (pinfunction "1_1") (pintype "passive"))
      (node (ref "TP10") (pin "1") (pinfunction "1_1") (pintype "bidirectional"))
      (node (ref "TP13") (pin "1") (pinfunction "1_1") (pintype "bidirectional"))
    )
    (net (code "68") (name "P3V3") (class "Default")
      (node (ref "C91") (pin "1") (pinfunction "1_1") (pintype "passive"))
      (node (ref "D2") (pin "2") (pinfunction "A_2") (pintype "passive"))
      (node (ref "D28") (pin "1") (pinfunction "C_1") (pintype "passive"))
      (node (ref "IC12") (pin "3") (pinfunction "EN_3") (pintype "input"))
      (node (ref "IC18") (pin "5") (pinfunction "EN/UVLO_5") (pintype "input"))
      (node (ref "L8") (pin "2") (pinfunction "2_2") (pintype "passive"))
      (node (ref "R101") (pin "1") (pinfunction "1_1") (pintype "passive"))
      (node (ref "R102") (pin "2") (pinfunction "2_2") (pintype "passive"))
      (node (ref "R121") (pin "2") (pinfunction "2_2") (pintype "passive"))
      (node (ref "R16") (pin "2") (pinfunction "2_2") (pintype "passive"))
      (node (ref "R67") (pin "2") (pinfunction "2_2") (pintype "passive"))
      (node (ref "R94") (pin "1") (pinfunction "1_1") (pintype "passive"))
      (node (ref "TP12") (pin "1") (pinfunction "1_1") (pintype "bidirectional"))
      (node (ref "TP8") (pin "1") (pinfunction "1_1") (pintype "bidirectional"))
    )
    (net (code "69") (name "P3V3IO") (class "Default")
      (node (ref "C115") (pin "2") (pinfunction "2_2") (pintype "passive"))
      (node (ref "IC12") (pin "5") (pinfunction "VOUT_5") (pintype "power_in"))
    )
    (net (code "70") (name "P3V3_MP") (class "Default")
      (node (ref "D2") (pin "1") (pinfunction "C_1") (pintype "passive"))
      (node (ref "R10") (pin "1") (pinfunction "1_1") (pintype "passive"))
    )
    (net (code "71") (name "P5V0") (class "Default")
      (node (ref "C10") (pin "2") (pinfunction "2_2") (pintype "passive"))
      (node (ref "C11") (pin "2") (pinfunction "2_2") (pintype "passive"))
      (node (ref "C118") (pin "2") (pinfunction "2_2") (pintype "passive"))
      (node (ref "C157") (pin "2") (pinfunction "2_2") (pintype "passive"))
      (node (ref "C158") (pin "2") (pinfunction "2_2") (pintype "passive"))
      (node (ref "C164") (pin "2") (pinfunction "2_2") (pintype "passive"))
      (node (ref "C165") (pin "1") (pinfunction "1_1") (pintype "passive"))
      (node (ref "C78") (pin "2") (pinfunction "2_2") (pintype "passive"))
      (node (ref "C8") (pin "2") (pinfunction "2_2") (pintype "passive"))
      (node (ref "C9") (pin "2") (pinfunction "2_2") (pintype "passive"))
      (node (ref "IC15") (pin "24") (pinfunction "VOUT_24") (pintype "output"))
      (node (ref "IC15") (pin "25") (pinfunction "VOUT_25") (pintype "output"))
      (node (ref "IC15") (pin "26") (pinfunction "VOUT_26") (pintype "output"))
      (node (ref "IC15") (pin "27") (pinfunction "VOUT_27") (pintype "output"))
      (node (ref "IC15") (pin "28") (pinfunction "VOUT_28") (pintype "output"))
      (node (ref "IC15") (pin "29") (pinfunction "VOUT_29") (pintype "output"))
      (node (ref "IC15") (pin "30") (pinfunction "VOUT_30") (pintype "output"))
      (node (ref "IC15") (pin "31") (pinfunction "VOUT_31") (pintype "output"))
      (node (ref "IC15") (pin "32") (pinfunction "VOUT_32") (pintype "output"))
      (node (ref "IC15") (pin "33") (pinfunction "VOUT_33") (pintype "output"))
      (node (ref "IC15") (pin "34") (pinfunction "VOUT_34") (pintype "output"))
      (node (ref "IC15") (pin "35") (pinfunction "VOUT_35") (pintype "output"))
      (node (ref "IC15") (pin "36") (pinfunction "VOUT_36") (pintype "output"))
      (node (ref "IC17") (pin "1") (pinfunction "EN_1") (pintype "input"))
      (node (ref "IC17") (pin "4") (pinfunction "VIN_4") (pintype "input"))
      (node (ref "IC34") (pin "C1") (pinfunction "VOUT_C1") (pintype "power_in"))
      (node (ref "IC34") (pin "D1") (pinfunction "VOUT_D1") (pintype "power_in"))
      (node (ref "IC34") (pin "D2") (pinfunction "VOUT_D2") (pintype "power_in"))
      (node (ref "IC34") (pin "E1") (pinfunction "VOUT_E1") (pintype "power_in"))
      (node (ref "IC34") (pin "E2") (pinfunction "VOUT_E2") (pintype "power_in"))
      (node (ref "IC35") (pin "C1") (pinfunction "VOUT_C1") (pintype "power_in"))
      (node (ref "IC35") (pin "D1") (pinfunction "VOUT_D1") (pintype "power_in"))
      (node (ref "IC35") (pin "D2") (pinfunction "VOUT_D2") (pintype "power_in"))
      (node (ref "IC35") (pin "E1") (pinfunction "VOUT_E1") (pintype "power_in"))
      (node (ref "IC35") (pin "E2") (pinfunction "VOUT_E2") (pintype "power_in"))
      (node (ref "IC37") (pin "C1") (pinfunction "VOUT_C1") (pintype "power_in"))
      (node (ref "IC37") (pin "D1") (pinfunction "VOUT_D1") (pintype "power_in"))
      (node (ref "IC37") (pin "D2") (pinfunction "VOUT_D2") (pintype "power_in"))
      (node (ref "IC37") (pin "E1") (pinfunction "VOUT_E1") (pintype "power_in"))
      (node (ref "IC37") (pin "E2") (pinfunction "VOUT_E2") (pintype "power_in"))
      (node (ref "R100") (pin "1") (pinfunction "1_1") (pintype "passive"))
      (node (ref "R124") (pin "1") (pinfunction "1_1") (pintype "passive"))
      (node (ref "R86") (pin "2") (pinfunction "2_2") (pintype "passive"))
      (node (ref "TP5") (pin "1") (pinfunction "1_1") (pintype "bidirectional"))
      (node (ref "TP7") (pin "1") (pinfunction "1_1") (pintype "bidirectional"))
    )
    (net (code "72") (name "P5V0A") (class "Default")
      (node (ref "C113") (pin "2") (pinfunction "2_2") (pintype "passive"))
      (node (ref "D25") (pin "1") (pinfunction "C_1") (pintype "passive"))
      (node (ref "IC18") (pin "1") (pinfunction "VOUT_1") (pintype "power_in"))
      (node (ref "IC18") (pin "2") (pinfunction "SENS_2") (pintype "input"))
      (node (ref "R39") (pin "1") (pinfunction "1_1") (pintype "passive"))
      (node (ref "TP11") (pin "1") (pinfunction "1_1") (pintype "bidirectional"))
      (node (ref "TP14") (pin "1") (pinfunction "1_1") (pintype "bidirectional"))
    )
    (net (code "73") (name "P12V0") (class "Default")
      (node (ref "C101") (pin "2") (pinfunction "2_2") (pintype "passive"))
      (node (ref "C117") (pin "2") (pinfunction "2_2") (pintype "passive"))
      (node (ref "C12") (pin "2") (pinfunction "2_2") (pintype "passive"))
      (node (ref "C13") (pin "2") (pinfunction "2_2") (pintype "passive"))
      (node (ref "C14") (pin "2") (pinfunction "2_2") (pintype "passive"))
      (node (ref "C15") (pin "1") (pinfunction "1_1") (pintype "passive"))
      (node (ref "C155") (pin "2") (pinfunction "2_2") (pintype "passive"))
      (node (ref "C156") (pin "2") (pinfunction "2_2") (pintype "passive"))
      (node (ref "C163") (pin "2") (pinfunction "2_2") (pintype "passive"))
      (node (ref "C166") (pin "2") (pinfunction "2_2") (pintype "passive"))
      (node (ref "C167") (pin "2") (pinfunction "2_2") (pintype "passive"))
      (node (ref "IC15") (pin "12") (pinfunction "PVIN_12") (pintype "input"))
      (node (ref "IC15") (pin "13") (pinfunction "PVIN_13") (pintype "input"))
      (node (ref "IC15") (pin "14") (pinfunction "PVIN_14") (pintype "input"))
      (node (ref "IC15") (pin "15") (pinfunction "PVIN_15") (pintype "input"))
      (node (ref "IC15") (pin "16") (pinfunction "PVIN_16") (pintype "input"))
      (node (ref "IC15") (pin "17") (pinfunction "PVIN_17") (pintype "input"))
      (node (ref "IC15") (pin "18") (pinfunction "PVIN_18") (pintype "input"))
      (node (ref "IC15") (pin "19") (pinfunction "PVIN_19") (pintype "input"))
      (node (ref "IC15") (pin "20") (pinfunction "PVIN_20") (pintype "input"))
      (node (ref "IC15") (pin "21") (pinfunction "PVIN_21") (pintype "input"))
      (node (ref "IC15") (pin "22") (pinfunction "PVIN_22") (pintype "input"))
      (node (ref "IC15") (pin "60") (pinfunction "VIN_60") (pintype "input"))
      (node (ref "IC22") (pin "4") (pinfunction "VIN+_4") (pintype "input"))
      (node (ref "IC34") (pin "A3") (pinfunction "RUN_A3") (pintype "input"))
      (node (ref "IC34") (pin "C5") (pinfunction "SVIN_C5") (pintype "power_in"))
      (node (ref "IC34") (pin "D5") (pinfunction "VIN_D5") (pintype "power_in"))
      (node (ref "IC34") (pin "E5") (pinfunction "VIN_E5") (pintype "power_in"))
      (node (ref "IC35") (pin "A3") (pinfunction "RUN_A3") (pintype "input"))
      (node (ref "IC35") (pin "C5") (pinfunction "SVIN_C5") (pintype "power_in"))
      (node (ref "IC35") (pin "D5") (pinfunction "VIN_D5") (pintype "power_in"))
      (node (ref "IC35") (pin "E5") (pinfunction "VIN_E5") (pintype "power_in"))
      (node (ref "IC37") (pin "A3") (pinfunction "RUN_A3") (pintype "input"))
      (node (ref "IC37") (pin "C5") (pinfunction "SVIN_C5") (pintype "power_in"))
      (node (ref "IC37") (pin "D5") (pinfunction "VIN_D5") (pintype "power_in"))
      (node (ref "IC37") (pin "E5") (pinfunction "VIN_E5") (pintype "power_in"))
      (node (ref "R128") (pin "1") (pinfunction "1_1") (pintype "passive"))
      (node (ref "R13") (pin "2") (pinfunction "2_2") (pintype "passive"))
      (node (ref "R138") (pin "1") (pinfunction "1_1") (pintype "passive"))
      (node (ref "R69") (pin "2") (pinfunction "2_2") (pintype "passive"))
      (node (ref "R88") (pin "1") (pinfunction "1_1") (pintype "passive"))
      (node (ref "R90") (pin "2") (pinfunction "2_2") (pintype "passive"))
      (node (ref "R97") (pin "1") (pinfunction "1_1") (pintype "passive"))
      (node (ref "T7") (pin "2") (pinfunction "S_2") (pintype "passive"))
      (node (ref "TP4") (pin "1") (pinfunction "1_1") (pintype "bidirectional"))
      (node (ref "TP6") (pin "1") (pinfunction "1_1") (pintype "bidirectional"))
    )
    (net (code "74") (name "P12V0_IN") (class "Default")
      (node (ref "B24") (pin "1") (pinfunction "1_1") (pintype "bidirectional"))
      (node (ref "D24") (pin "1") (pinfunction "C_1") (pintype "passive"))
      (node (ref "IC22") (pin "5") (pinfunction "V+_5") (pintype "power_in"))
      (node (ref "J4") (pin "3") (pinfunction "3_3") (pintype "bidirectional"))
      (node (ref "J5") (pin "3") (pinfunction "3_3") (pintype "bidirectional"))
      (node (ref "J5") (pin "4") (pinfunction "4_4") (pintype "bidirectional"))
      (node (ref "R131") (pin "2") (pinfunction "2_2") (pintype "passive"))
      (node (ref "R69") (pin "1") (pinfunction "1_1") (pintype "passive"))
      (node (ref "T3") (pin "1") (pinfunction "S_1") (pintype "passive"))
      (node (ref "T3") (pin "2") (pinfunction "S_2") (pintype "passive"))
      (node (ref "T3") (pin "3") (pinfunction "S_3") (pintype "passive"))
      (node (ref "T5") (pin "1") (pinfunction "E_1") (pintype "passive"))
    )
    (net (code "75") (name "unconnected-(IC3-ADJ-Pad9)") (class "Default")
      (node (ref "IC3") (pin "9") (pinfunction "ADJ_9") (pintype "input+no_connect"))
    )
    (net (code "76") (name "unconnected-(IC12-NC-Pad4)") (class "Default")
      (node (ref "IC12") (pin "4") (pinfunction "NC_4") (pintype "passive+no_connect"))
    )
    (net (code "77") (name "unconnected-(IC15-BST-Pad52)") (class "Default")
      (node (ref "IC15") (pin "52") (pinfunction "BST_52") (pintype "passive+no_connect"))
    )
    (net (code "78") (name "unconnected-(IC15-BST-Pad53)") (class "Default")
      (node (ref "IC15") (pin "53") (pinfunction "BST_53") (pintype "passive+no_connect"))
    )
    (net (code "79") (name "unconnected-(IC15-BST-Pad54)") (class "Default")
      (node (ref "IC15") (pin "54") (pinfunction "BST_54") (pintype "passive+no_connect"))
    )
    (net (code "80") (name "unconnected-(IC15-NC-Pad55)") (class "Default")
      (node (ref "IC15") (pin "55") (pinfunction "NC_55") (pintype "passive+no_connect"))
    )
    (net (code "81") (name "unconnected-(IC15-PG-Pad58)") (class "Default")
      (node (ref "IC15") (pin "58") (pinfunction "PG_58") (pintype "output+no_connect"))
    )
    (net (code "82") (name "unconnected-(IC15-RIA-Pad46)") (class "Default")
      (node (ref "IC15") (pin "46") (pinfunction "RIA_46") (pintype "passive+no_connect"))
    )
    (net (code "83") (name "unconnected-(IC15-RIA-Pad47)") (class "Default")
      (node (ref "IC15") (pin "47") (pinfunction "RIA_47") (pintype "passive+no_connect"))
    )
    (net (code "84") (name "unconnected-(IC16-NC-Pad3)") (class "Default")
      (node (ref "IC16") (pin "3") (pinfunction "NC_3") (pintype "passive+no_connect"))
    )
    (net (code "85") (name "unconnected-(IC16-TRIM-Pad5)") (class "Default")
      (node (ref "IC16") (pin "5") (pinfunction "TRIM_5") (pintype "passive+no_connect"))
    )
    (net (code "86") (name "unconnected-(IC18-NC-Pad4)") (class "Default")
      (node (ref "IC18") (pin "4") (pinfunction "NC_4") (pintype "passive+no_connect"))
    )
    (net (code "87") (name "unconnected-(IC18-PG-Pad7)") (class "Default")
      (node (ref "IC18") (pin "7") (pinfunction "PG_7") (pintype "output+no_connect"))
    )
    (net (code "88") (name "unconnected-(IC34-CLKIN-PadA5)") (class "Default")
      (node (ref "IC34") (pin "A5") (pinfunction "CLKIN_A5") (pintype "input+no_connect"))
    )
    (net (code "89") (name "unconnected-(IC37-CLKOUT-PadB5)") (class "Default")
      (node (ref "IC37") (pin "B5") (pinfunction "CLKOUT_B5") (pintype "output"))
    )
    (net (code "90") (name "unconnected-(IC37-PHMODE-PadB2)") (class "Default")
      (node (ref "IC37") (pin "B2") (pinfunction "PHMODE_B2") (pintype "input+no_connect"))
    )
    (net (code "91") (name "unconnected-(J4-Pad2)") (class "Default")
      (node (ref "J4") (pin "2") (pinfunction "2_2") (pintype "bidirectional"))
    )
  )
)
